# CCM_0001.net
KiCad netlist of a schematic drawn in EAGLE
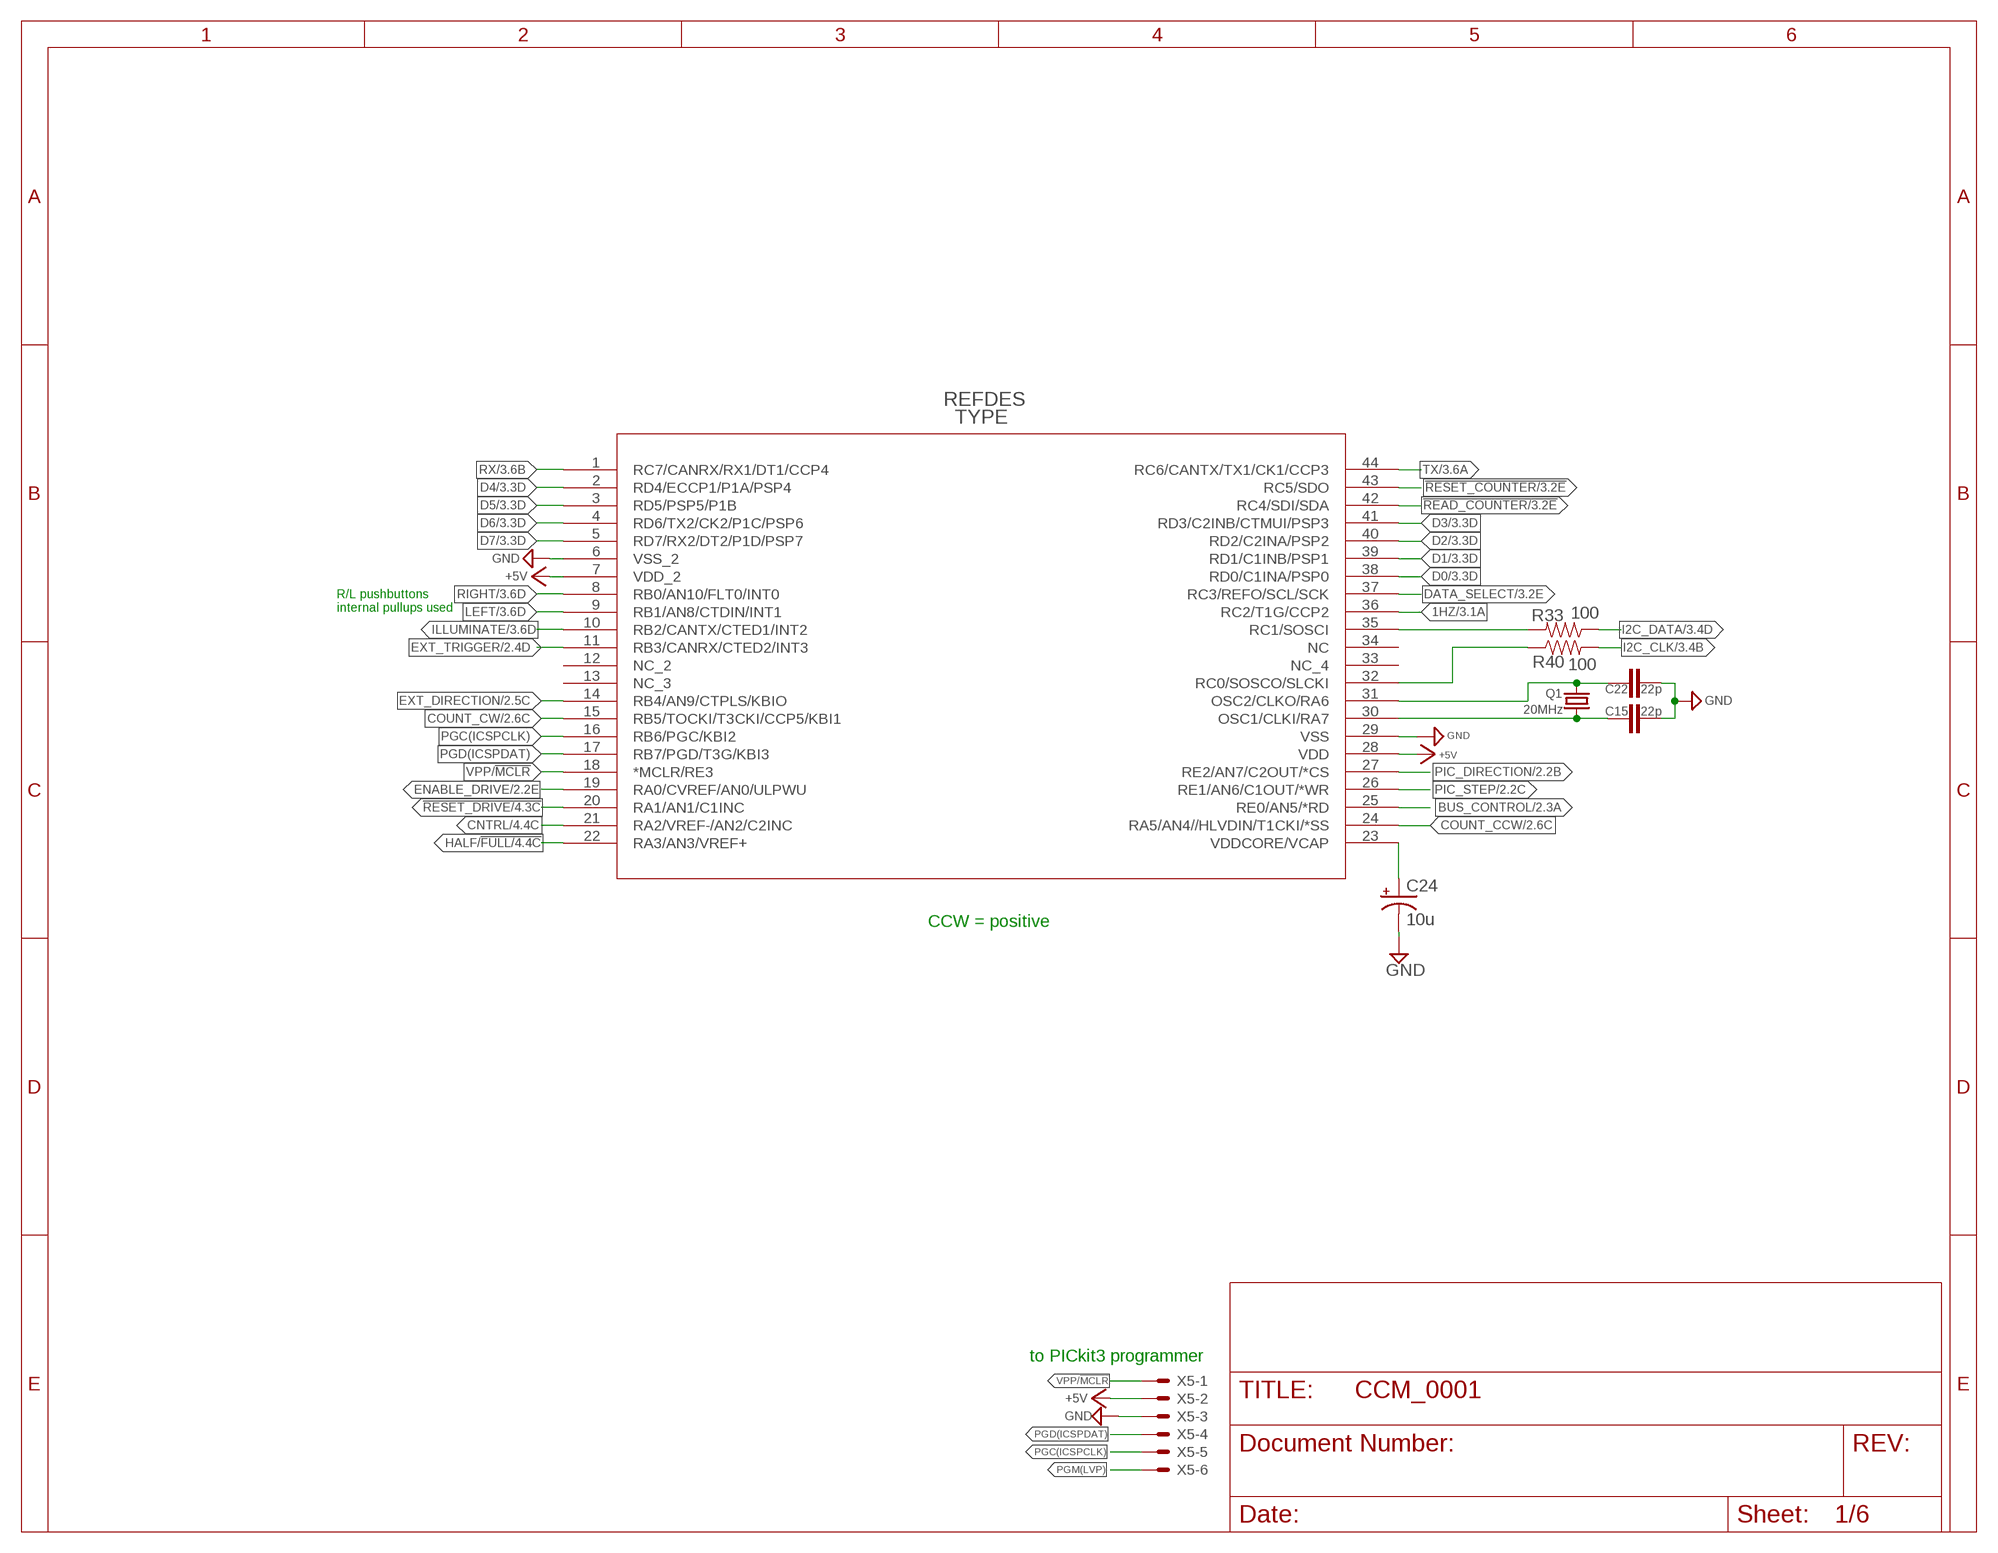
[diagram p0: schematic, sheet 1]
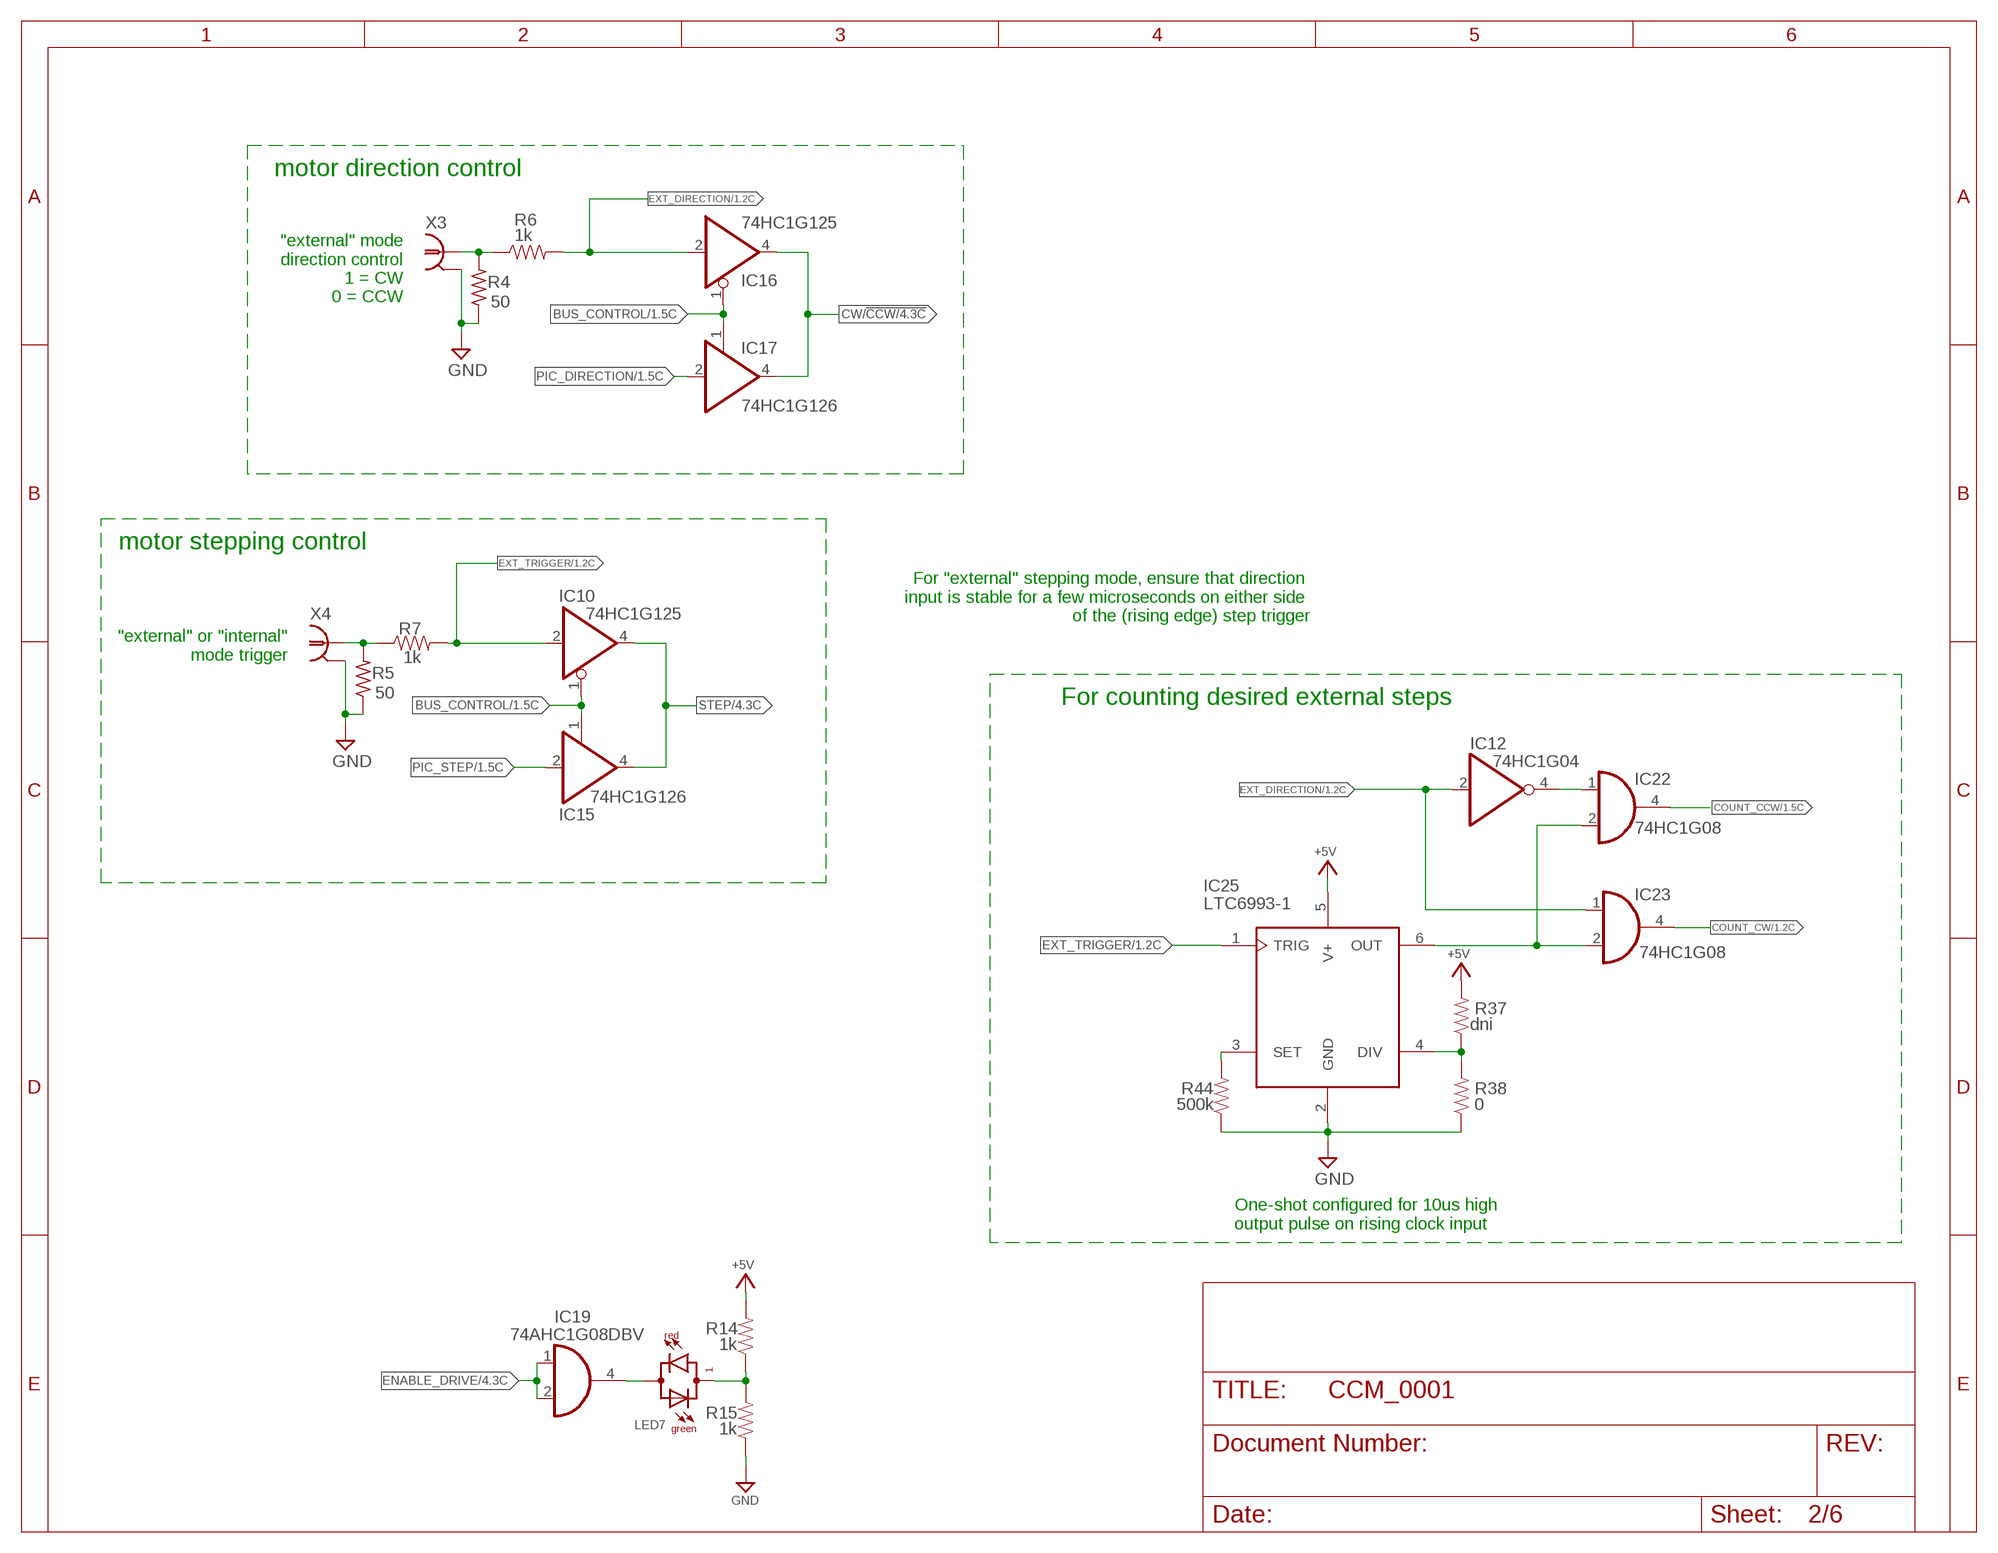
[diagram p1: schematic, sheet 2]
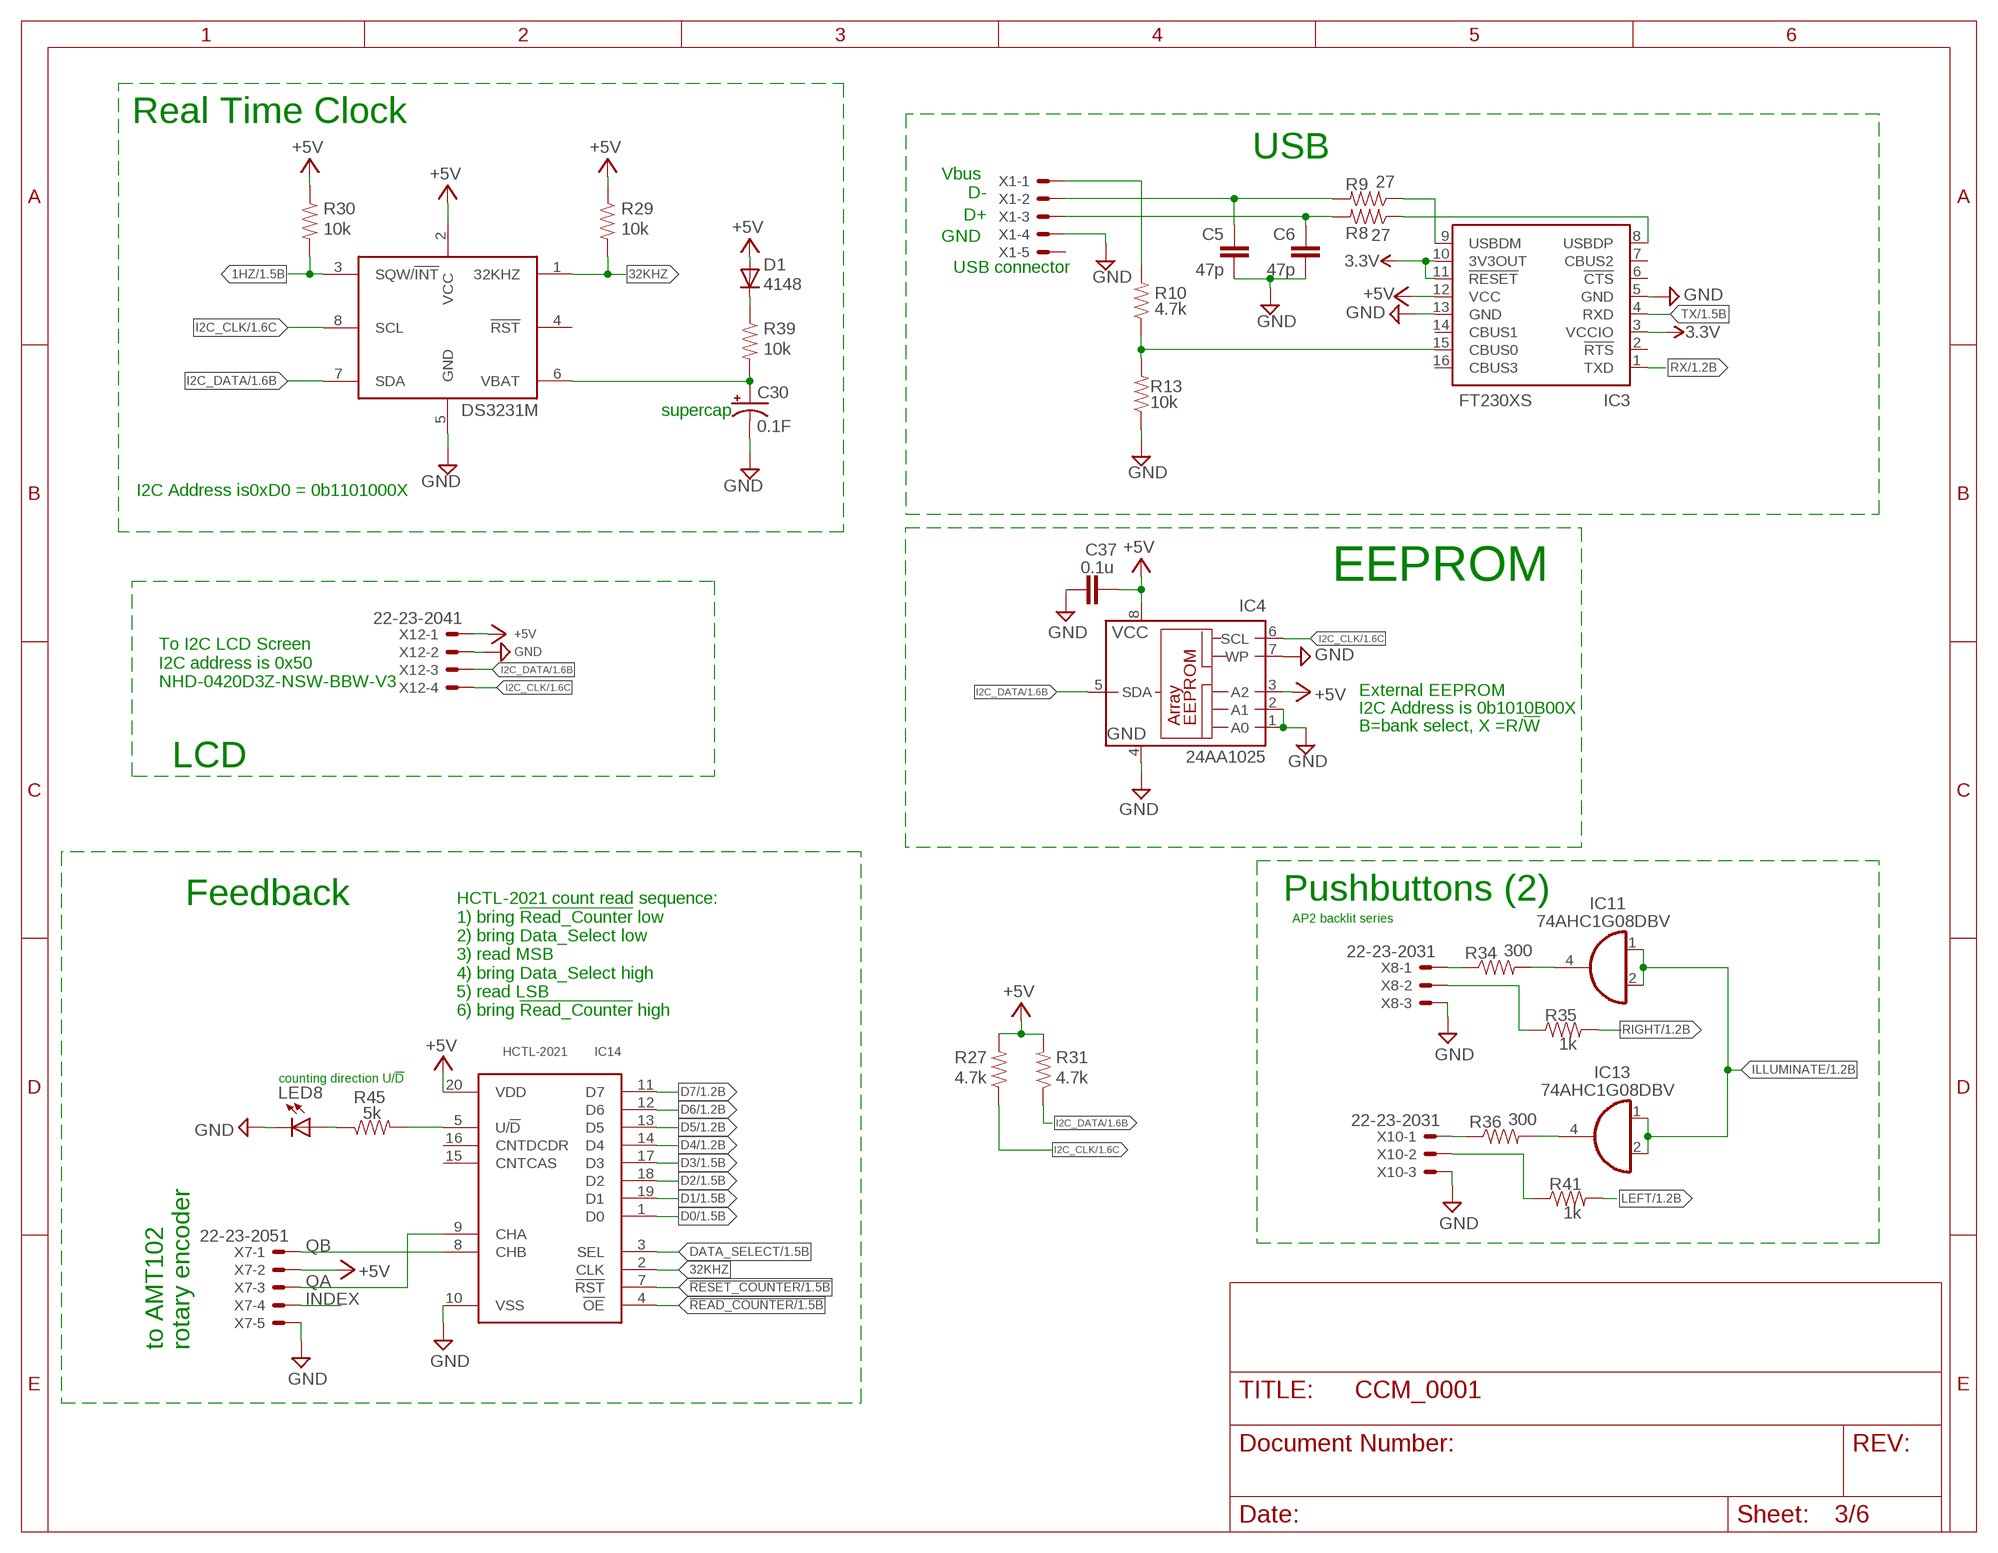
[diagram p2: schematic, sheet 3]
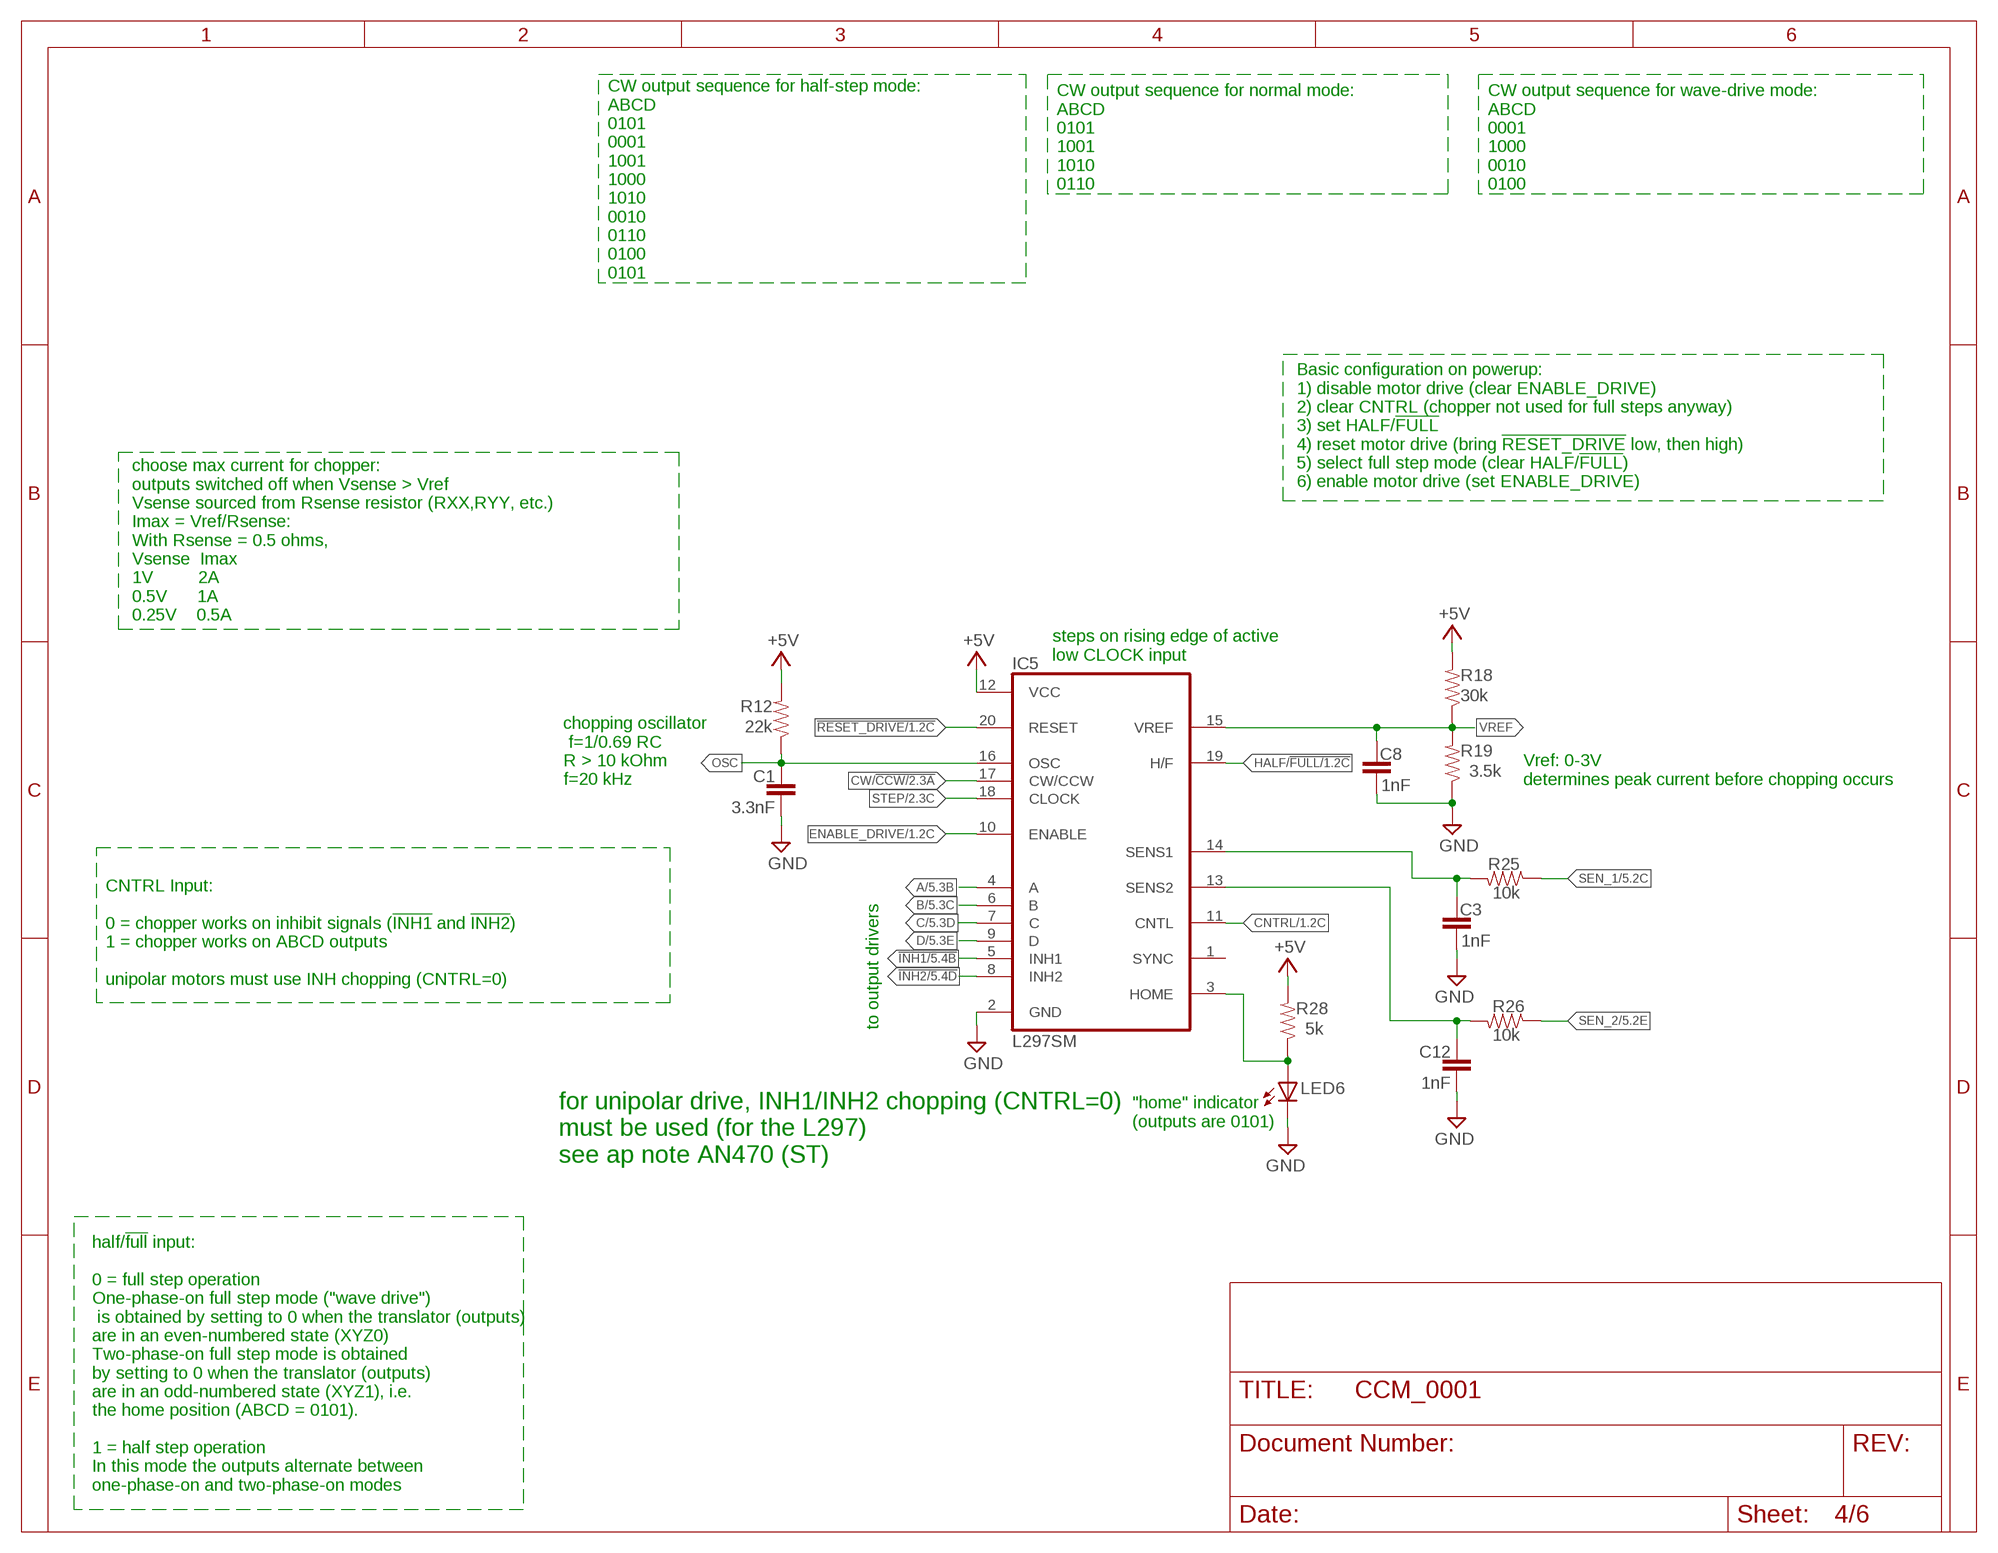
[diagram p3: schematic, sheet 4]
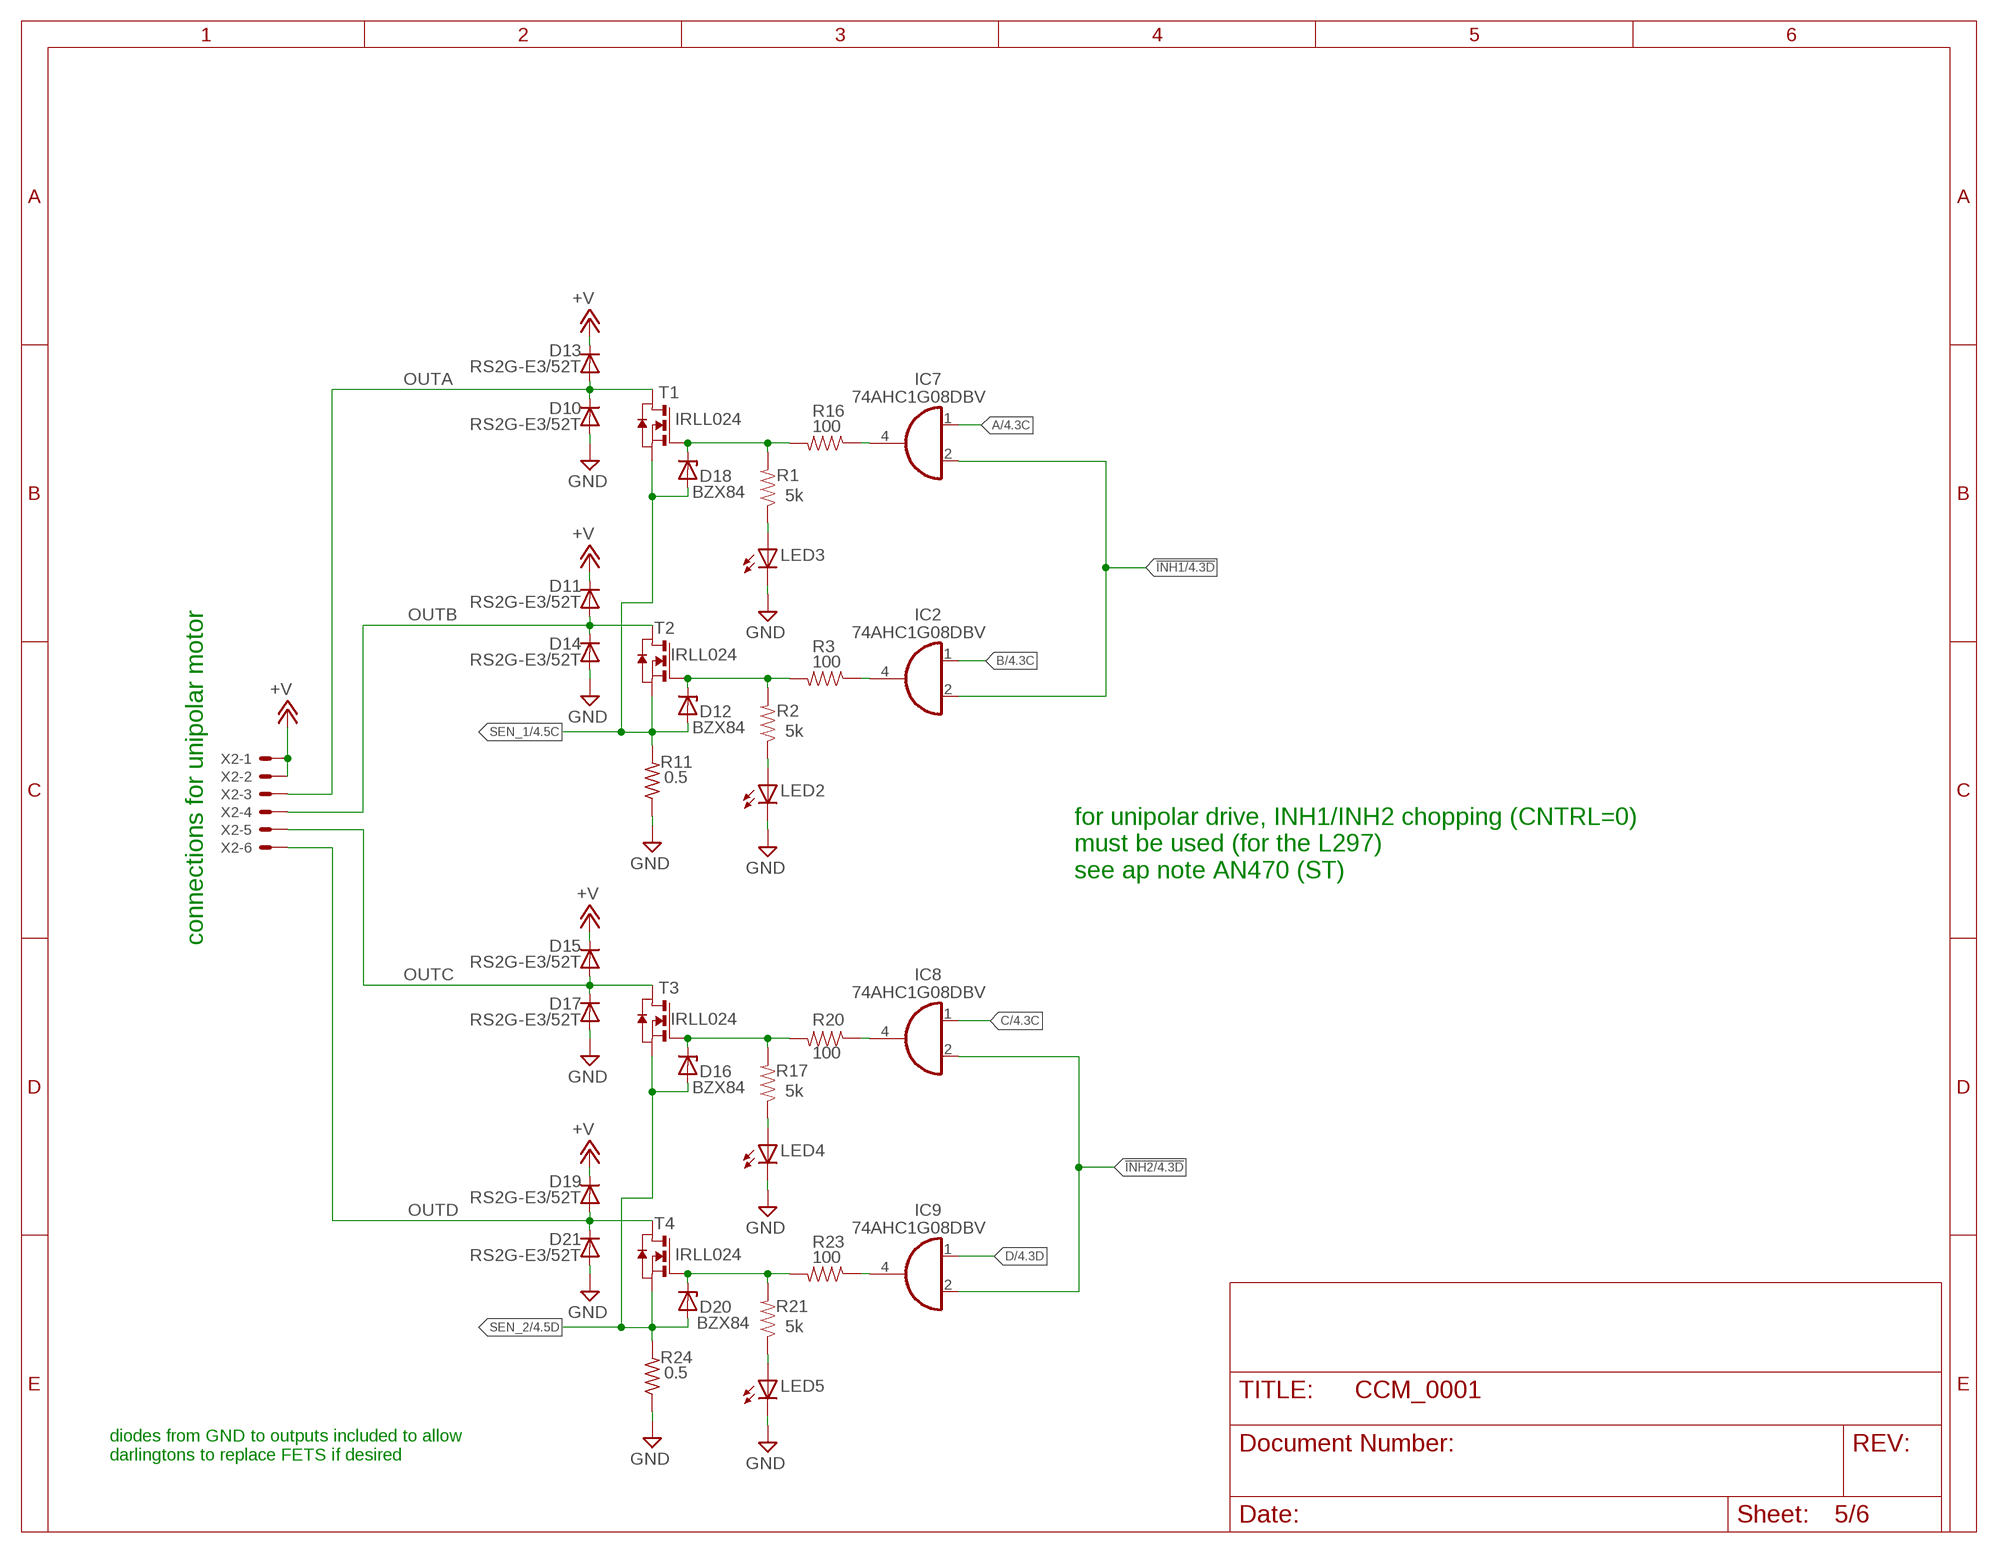
[diagram p4: schematic, sheet 5]
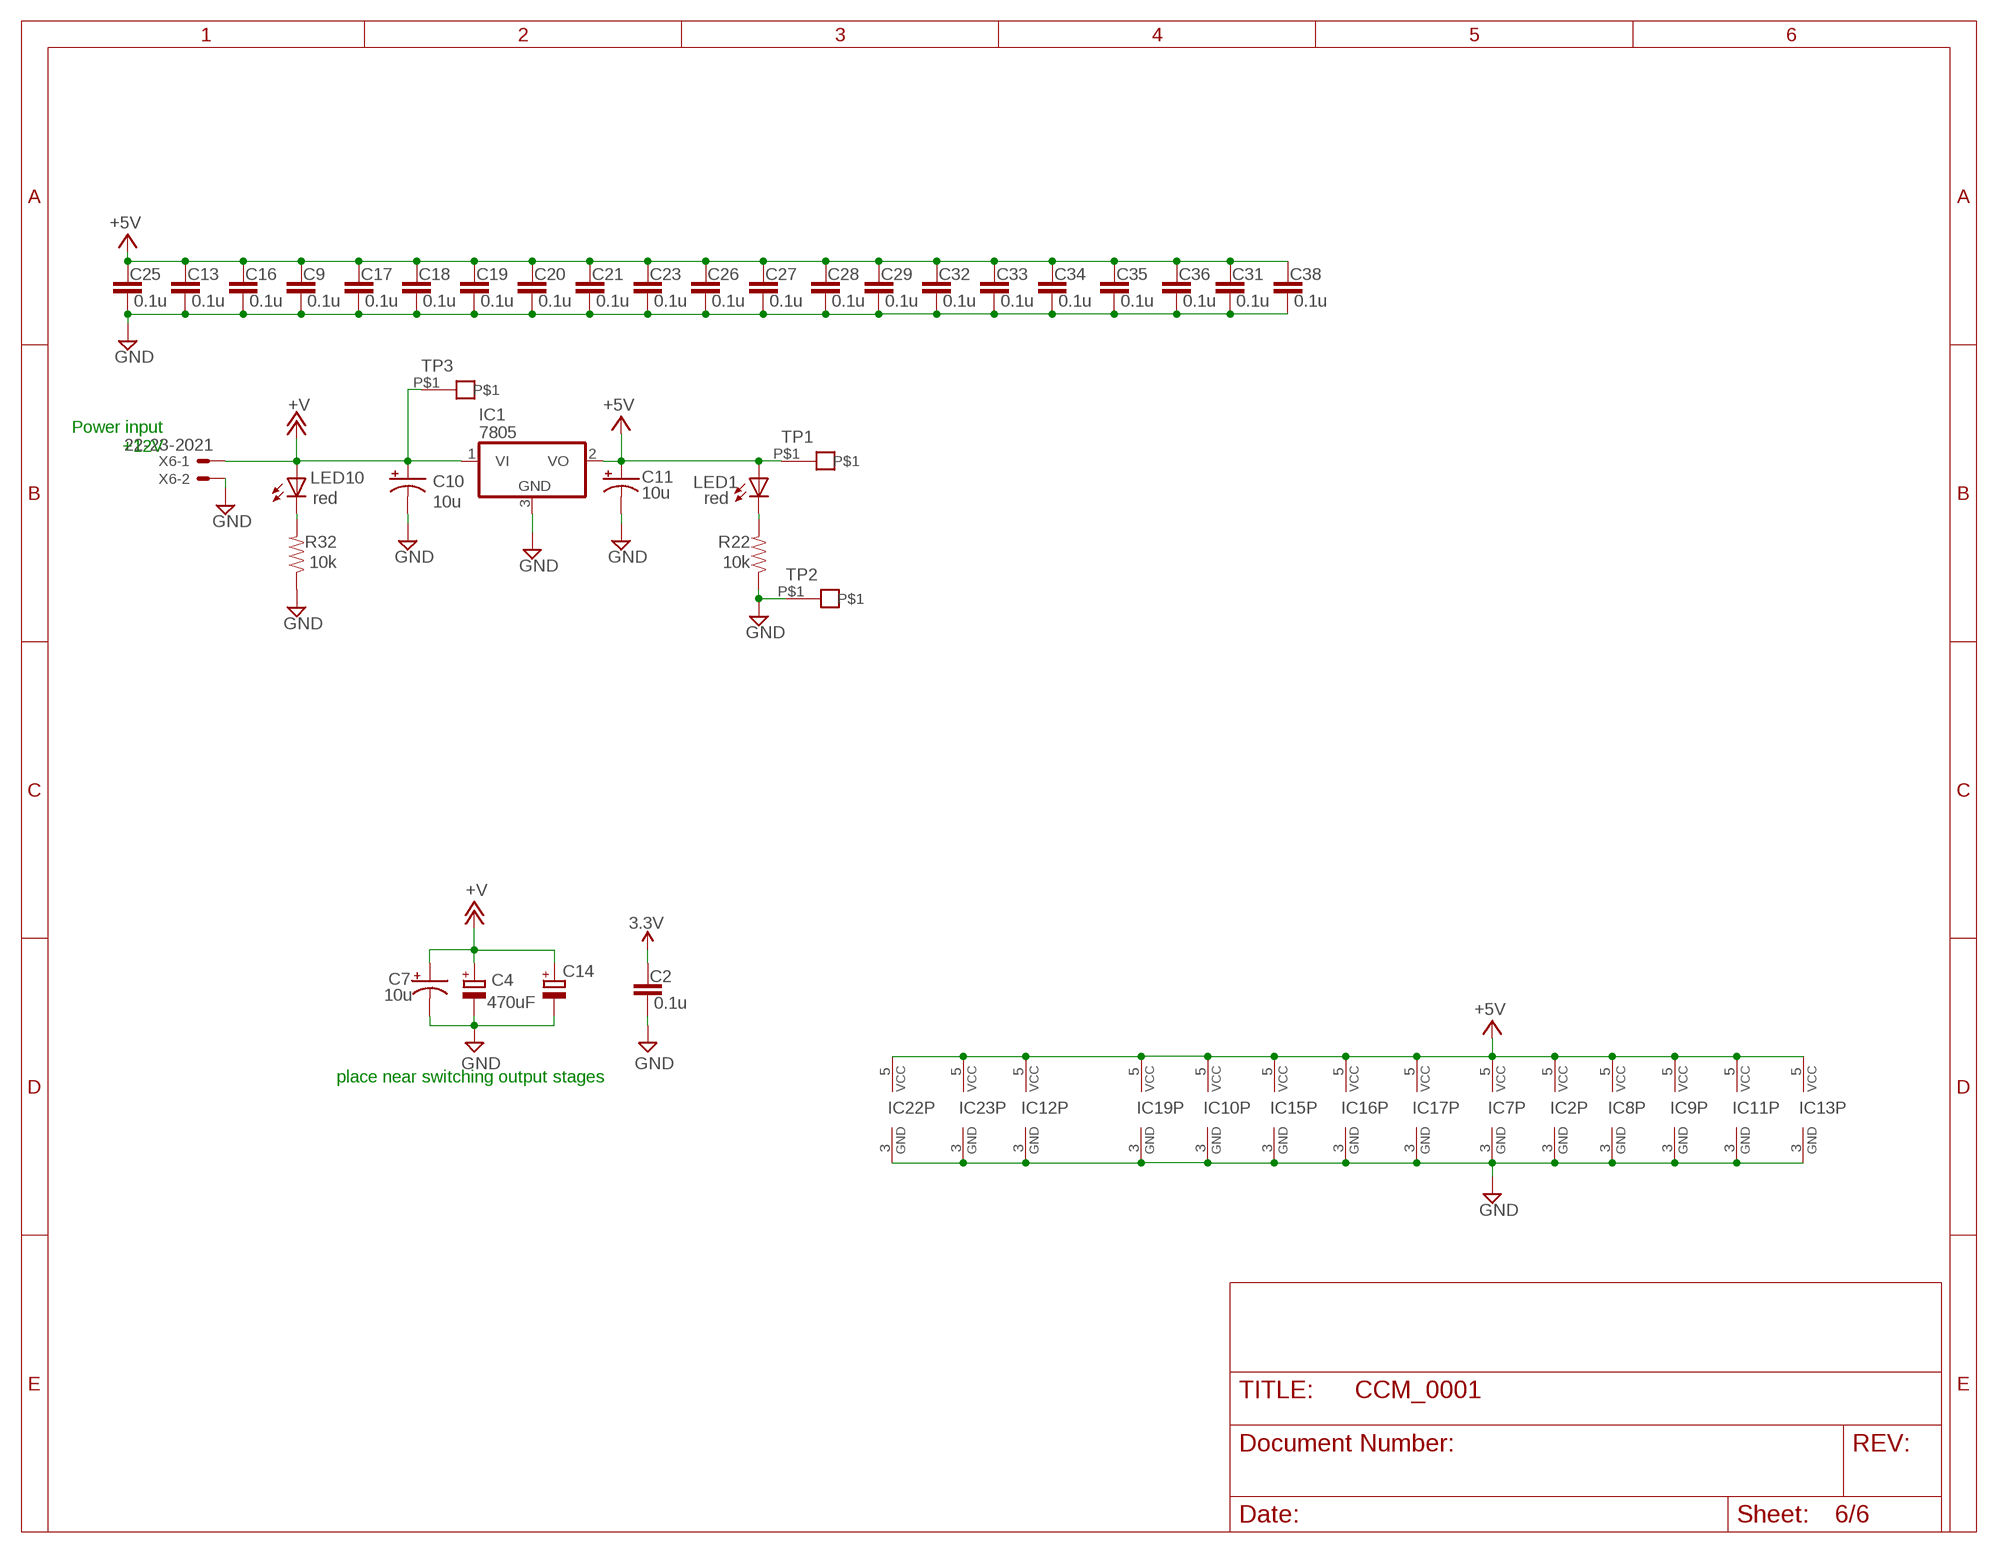
[diagram p5: schematic, sheet 6]

(export (version "E")
  (design (tool "Eeschema 10.0.6"))
  (components
    (comp (ref "C1")
      (value "3.3nF")
      (footprint "eagle-import:0603-CAP")
      (libsource (lib "eagle-import") (part "CAP0603-CAP"))
    )
    (comp (ref "C3")
      (value "1nF")
      (footprint "eagle-import:0603-CAP")
      (libsource (lib "eagle-import") (part "CAP0603-CAP"))
    )
    (comp (ref "C8")
      (value "1nF")
      (footprint "eagle-import:0603-CAP")
      (libsource (lib "eagle-import") (part "CAP0603-CAP"))
    )
    (comp (ref "C12")
      (value "1nF")
      (footprint "eagle-import:0603-CAP")
      (libsource (lib "eagle-import") (part "CAP0603-CAP"))
    )
    (comp (ref "IC5")
      (value "L297SM")
      (footprint "eagle-import:SO20")
      (libsource (lib "eagle-import") (part "L297SM"))
    )
    (comp (ref "LED6")
      (value "red")
      (footprint "eagle-import:CHIPLED_0603")
      (libsource (lib "eagle-import") (part "LEDCHIPLED_0603"))
    )
    (comp (ref "R12")
      (value "22k")
      (footprint "eagle-import:0603-RES")
      (libsource (lib "eagle-import") (part "RESISTOR0603-RES"))
    )
    (comp (ref "R18")
      (value "30k")
      (footprint "eagle-import:0603-RES")
      (libsource (lib "eagle-import") (part "RESISTOR0603-RES"))
    )
    (comp (ref "R19")
      (value "3.5k")
      (footprint "eagle-import:0603-RES")
      (libsource (lib "eagle-import") (part "RESISTOR0603-RES"))
    )
    (comp (ref "R25")
      (value "10k")
      (footprint "eagle-import:0603-RES")
      (libsource (lib "eagle-import") (part "RESISTOR0603-RES"))
    )
    (comp (ref "R26")
      (value "10k")
      (footprint "eagle-import:0603-RES")
      (libsource (lib "eagle-import") (part "RESISTOR0603-RES"))
    )
    (comp (ref "R28")
      (value "5k")
      (footprint "eagle-import:0603-RES")
      (libsource (lib "eagle-import") (part "RESISTOR0603-RES"))
    )
    (comp (ref "C15")
      (value "22p")
      (footprint "eagle-import:0603-CAP")
      (libsource (lib "eagle-import") (part "CAP0603-CAP"))
    )
    (comp (ref "C22")
      (value "22p")
      (footprint "eagle-import:0603-CAP")
      (libsource (lib "eagle-import") (part "CAP0603-CAP"))
    )
    (comp (ref "C24")
      (value "10u")
      (footprint "eagle-import:EIA3216")
      (libsource (lib "eagle-import") (part "CAP_POL1206"))
    )
    (comp (ref "IC18")
      (value "PIC18F46K80")
      (footprint "eagle-import:TQFP44_MC")
      (libsource (lib "eagle-import") (part "PIC18F46K80"))
    )
    (comp (ref "Q1")
      (value "20MHz")
      (footprint "eagle-import:TC26V")
      (libsource (lib "eagle-import") (part "CRYSTALTC26V"))
    )
    (comp (ref "R33")
      (value "100")
      (footprint "eagle-import:0603-RES")
      (libsource (lib "eagle-import") (part "RESISTOR0603-RES"))
    )
    (comp (ref "R40")
      (value "100")
      (footprint "eagle-import:0603-RES")
      (libsource (lib "eagle-import") (part "RESISTOR0603-RES"))
    )
    (comp (ref "X5")
      (value "22-23-2061")
      (footprint "eagle-import:22-23-2061")
      (fields (field (name "MF") "MOLEX"))
      (libsource (lib "eagle-import") (part "22-23-2061"))
    )
    (comp (ref "C5")
      (value "47p")
      (footprint "eagle-import:0603-CAP")
      (libsource (lib "eagle-import") (part "CAP0603-CAP"))
    )
    (comp (ref "C6")
      (value "47p")
      (footprint "eagle-import:0603-CAP")
      (libsource (lib "eagle-import") (part "CAP0603-CAP"))
    )
    (comp (ref "C30")
      (value "0.1F")
      (footprint "eagle-import:P128-60")
      (libsource (lib "eagle-import") (part "CPOL-USP128-60"))
    )
    (comp (ref "C37")
      (value "0.1u")
      (footprint "eagle-import:0603-CAP")
      (libsource (lib "eagle-import") (part "CAP0603-CAP"))
    )
    (comp (ref "D1")
      (value "4148")
      (footprint "eagle-import:SOT23-3")
      (libsource (lib "eagle-import") (part "DIODESOT23"))
    )
    (comp (ref "IC3")
      (value "FT230XS")
      (footprint "eagle-import:SSOP16")
      (libsource (lib "eagle-import") (part "FT230XS"))
    )
    (comp (ref "IC4")
      (value "24AA1025")
      (footprint "eagle-import:SO-08")
      (fields (field (name "MF") "MICROCHIP") (field (name "MPN") "24AA16-I/SN"))
      (libsource (lib "eagle-import") (part "24SNAA16"))
    )
    (comp (ref "IC6")
      (value "DS3231M")
      (footprint "eagle-import:8-SOIC")
      (libsource (lib "eagle-import") (part "DS3231M"))
    )
    (comp (ref "IC11")
      (value "74AHC1G08DBV")
      (footprint "eagle-import:SOT23-5")
      (libsource (lib "eagle-import") (part "741G08DBVAHC"))
    )
    (comp (ref "IC13")
      (value "74AHC1G08DBV")
      (footprint "eagle-import:SOT23-5")
      (libsource (lib "eagle-import") (part "741G08DBVAHC"))
    )
    (comp (ref "IC14")
      (value "HCTL-2021")
      (footprint "eagle-import:PLCC20")
      (libsource (lib "eagle-import") (part "HCTL-2021"))
    )
    (comp (ref "LED8")
      (value "red")
      (footprint "eagle-import:CHIPLED_0603")
      (libsource (lib "eagle-import") (part "LEDCHIPLED_0603"))
    )
    (comp (ref "R8")
      (value "27")
      (footprint "eagle-import:0603-RES")
      (libsource (lib "eagle-import") (part "RESISTOR0603-RES"))
    )
    (comp (ref "R9")
      (value "27")
      (footprint "eagle-import:0603-RES")
      (libsource (lib "eagle-import") (part "RESISTOR0603-RES"))
    )
    (comp (ref "R10")
      (value "4.7k")
      (footprint "eagle-import:0603-RES")
      (libsource (lib "eagle-import") (part "RESISTOR0603-RES"))
    )
    (comp (ref "R13")
      (value "10k")
      (footprint "eagle-import:0603-RES")
      (libsource (lib "eagle-import") (part "RESISTOR0603-RES"))
    )
    (comp (ref "R27")
      (value "4.7k")
      (footprint "eagle-import:0603-RES")
      (libsource (lib "eagle-import") (part "RESISTOR0603-RES"))
    )
    (comp (ref "R29")
      (value "10k")
      (footprint "eagle-import:0603-RES")
      (libsource (lib "eagle-import") (part "RESISTOR0603-RES"))
    )
    (comp (ref "R30")
      (value "10k")
      (footprint "eagle-import:0603-RES")
      (libsource (lib "eagle-import") (part "RESISTOR0603-RES"))
    )
    (comp (ref "R31")
      (value "4.7k")
      (footprint "eagle-import:0603-RES")
      (libsource (lib "eagle-import") (part "RESISTOR0603-RES"))
    )
    (comp (ref "R34")
      (value "300")
      (footprint "eagle-import:0603-RES")
      (libsource (lib "eagle-import") (part "RESISTOR0603-RES"))
    )
    (comp (ref "R35")
      (value "1k")
      (footprint "eagle-import:0603-RES")
      (libsource (lib "eagle-import") (part "RESISTOR0603-RES"))
    )
    (comp (ref "R36")
      (value "300")
      (footprint "eagle-import:0603-RES")
      (libsource (lib "eagle-import") (part "RESISTOR0603-RES"))
    )
    (comp (ref "R39")
      (value "10k")
      (footprint "eagle-import:0603-RES")
      (libsource (lib "eagle-import") (part "RESISTOR0603-RES"))
    )
    (comp (ref "R41")
      (value "1k")
      (footprint "eagle-import:0603-RES")
      (libsource (lib "eagle-import") (part "RESISTOR0603-RES"))
    )
    (comp (ref "R45")
      (value "5k")
      (footprint "eagle-import:0603-RES")
      (libsource (lib "eagle-import") (part "RESISTOR0603-RES"))
    )
    (comp (ref "X1")
      (value "22-23-2051")
      (footprint "eagle-import:22-23-2051")
      (fields (field (name "MF") "MOLEX"))
      (libsource (lib "eagle-import") (part "22-23-2051"))
    )
    (comp (ref "X7")
      (value "22-23-2051")
      (footprint "eagle-import:22-23-2051")
      (fields (field (name "MF") "MOLEX"))
      (libsource (lib "eagle-import") (part "22-23-2051"))
    )
    (comp (ref "X8")
      (value "22-23-2031")
      (footprint "eagle-import:22-23-2031")
      (fields (field (name "MF") "MOLEX"))
      (libsource (lib "eagle-import") (part "22-23-2031"))
    )
    (comp (ref "X10")
      (value "22-23-2031")
      (footprint "eagle-import:22-23-2031")
      (fields (field (name "MF") "MOLEX"))
      (libsource (lib "eagle-import") (part "22-23-2031"))
    )
    (comp (ref "X12")
      (value "22-23-2041")
      (footprint "eagle-import:22-23-2041")
      (fields (field (name "MF") "MOLEX"))
      (libsource (lib "eagle-import") (part "22-23-2041"))
    )
    (comp (ref "C2")
      (value "0.1u")
      (footprint "eagle-import:0603-CAP")
      (libsource (lib "eagle-import") (part "CAP0603-CAP"))
    )
    (comp (ref "C4")
      (value "470uF")
      (footprint "eagle-import:SANYO-OSCON_SMD_F8")
      (libsource (lib "eagle-import") (part "CPOL-EUSANYO_SMD_F8"))
    )
    (comp (ref "C7")
      (value "10u")
      (footprint "eagle-import:EIA3216")
      (libsource (lib "eagle-import") (part "CAP_POL1206"))
    )
    (comp (ref "C9")
      (value "0.1u")
      (footprint "eagle-import:0603-CAP")
      (libsource (lib "eagle-import") (part "CAP0603-CAP"))
    )
    (comp (ref "C10")
      (value "10u")
      (footprint "eagle-import:EIA3216")
      (libsource (lib "eagle-import") (part "CAP_POL1206"))
    )
    (comp (ref "C11")
      (value "10u")
      (footprint "eagle-import:EIA3216")
      (libsource (lib "eagle-import") (part "CAP_POL1206"))
    )
    (comp (ref "C13")
      (value "0.1u")
      (footprint "eagle-import:0603-CAP")
      (libsource (lib "eagle-import") (part "CAP0603-CAP"))
    )
    (comp (ref "C14")
      (value "CPOL-EUE5-13")
      (footprint "eagle-import:E5-13")
      (libsource (lib "eagle-import") (part "resistor_CPOL-EUE5-13"))
    )
    (comp (ref "C16")
      (value "0.1u")
      (footprint "eagle-import:0603-CAP")
      (libsource (lib "eagle-import") (part "CAP0603-CAP"))
    )
    (comp (ref "C17")
      (value "0.1u")
      (footprint "eagle-import:0603-CAP")
      (libsource (lib "eagle-import") (part "CAP0603-CAP"))
    )
    (comp (ref "C18")
      (value "0.1u")
      (footprint "eagle-import:0603-CAP")
      (libsource (lib "eagle-import") (part "CAP0603-CAP"))
    )
    (comp (ref "C19")
      (value "0.1u")
      (footprint "eagle-import:0603-CAP")
      (libsource (lib "eagle-import") (part "CAP0603-CAP"))
    )
    (comp (ref "C20")
      (value "0.1u")
      (footprint "eagle-import:0603-CAP")
      (libsource (lib "eagle-import") (part "CAP0603-CAP"))
    )
    (comp (ref "C21")
      (value "0.1u")
      (footprint "eagle-import:0603-CAP")
      (libsource (lib "eagle-import") (part "CAP0603-CAP"))
    )
    (comp (ref "C23")
      (value "0.1u")
      (footprint "eagle-import:0603-CAP")
      (libsource (lib "eagle-import") (part "CAP0603-CAP"))
    )
    (comp (ref "C25")
      (value "0.1u")
      (footprint "eagle-import:0603-CAP")
      (libsource (lib "eagle-import") (part "CAP0603-CAP"))
    )
    (comp (ref "C26")
      (value "0.1u")
      (footprint "eagle-import:0603-CAP")
      (libsource (lib "eagle-import") (part "CAP0603-CAP"))
    )
    (comp (ref "C27")
      (value "0.1u")
      (footprint "eagle-import:0603-CAP")
      (libsource (lib "eagle-import") (part "CAP0603-CAP"))
    )
    (comp (ref "C28")
      (value "0.1u")
      (footprint "eagle-import:0603-CAP")
      (libsource (lib "eagle-import") (part "CAP0603-CAP"))
    )
    (comp (ref "C29")
      (value "0.1u")
      (footprint "eagle-import:0603-CAP")
      (libsource (lib "eagle-import") (part "CAP0603-CAP"))
    )
    (comp (ref "C31")
      (value "0.1u")
      (footprint "eagle-import:0603-CAP")
      (libsource (lib "eagle-import") (part "CAP0603-CAP"))
    )
    (comp (ref "C32")
      (value "0.1u")
      (footprint "eagle-import:0603-CAP")
      (libsource (lib "eagle-import") (part "CAP0603-CAP"))
    )
    (comp (ref "C33")
      (value "0.1u")
      (footprint "eagle-import:0603-CAP")
      (libsource (lib "eagle-import") (part "CAP0603-CAP"))
    )
    (comp (ref "C34")
      (value "0.1u")
      (footprint "eagle-import:0603-CAP")
      (libsource (lib "eagle-import") (part "CAP0603-CAP"))
    )
    (comp (ref "C35")
      (value "0.1u")
      (footprint "eagle-import:0603-CAP")
      (libsource (lib "eagle-import") (part "CAP0603-CAP"))
    )
    (comp (ref "C36")
      (value "0.1u")
      (footprint "eagle-import:0603-CAP")
      (libsource (lib "eagle-import") (part "CAP0603-CAP"))
    )
    (comp (ref "C38")
      (value "0.1u")
      (footprint "eagle-import:0603-CAP")
      (libsource (lib "eagle-import") (part "CAP0603-CAP"))
    )
    (comp (ref "IC1")
      (value "7805")
      (footprint "eagle-import:TO252")
      (libsource (lib "eagle-import") (part "78DT24"))
    )
    (comp (ref "IC2")
      (value "74AHC1G08DBV")
      (footprint "eagle-import:SOT23-5")
      (libsource (lib "eagle-import") (part "741G08DBVAHC"))
    )
    (comp (ref "IC7")
      (value "74AHC1G08DBV")
      (footprint "eagle-import:SOT23-5")
      (libsource (lib "eagle-import") (part "741G08DBVAHC"))
    )
    (comp (ref "IC8")
      (value "74AHC1G08DBV")
      (footprint "eagle-import:SOT23-5")
      (libsource (lib "eagle-import") (part "741G08DBVAHC"))
    )
    (comp (ref "IC9")
      (value "74AHC1G08DBV")
      (footprint "eagle-import:SOT23-5")
      (libsource (lib "eagle-import") (part "741G08DBVAHC"))
    )
    (comp (ref "IC10")
      (value "74HC1G125")
      (footprint "eagle-import:SOT23-5")
      (libsource (lib "eagle-import") (part "741G125DBVAHC"))
    )
    (comp (ref "IC12")
      (value "74HC1G04")
      (footprint "eagle-import:SOT23-5")
      (libsource (lib "eagle-import") (part "741G04DBVAHC"))
    )
    (comp (ref "IC15")
      (value "74HC1G126")
      (footprint "eagle-import:SOT23-5")
      (libsource (lib "eagle-import") (part "741G126DBVAHC"))
    )
    (comp (ref "IC16")
      (value "74HC1G125")
      (footprint "eagle-import:SOT23-5")
      (libsource (lib "eagle-import") (part "741G125DBVAHC"))
    )
    (comp (ref "IC17")
      (value "74HC1G126")
      (footprint "eagle-import:SOT23-5")
      (libsource (lib "eagle-import") (part "741G126DBVAHC"))
    )
    (comp (ref "IC19")
      (value "74AHC1G08DBV")
      (footprint "eagle-import:SOT23-5")
      (libsource (lib "eagle-import") (part "741G08DBVAHC"))
    )
    (comp (ref "IC22")
      (value "74HC1G08")
      (footprint "eagle-import:SOT23-5")
      (libsource (lib "eagle-import") (part "741G08DBVAHC"))
    )
    (comp (ref "IC23")
      (value "74HC1G08")
      (footprint "eagle-import:SOT23-5")
      (libsource (lib "eagle-import") (part "741G08DBVAHC"))
    )
    (comp (ref "LED1")
      (value "red")
      (footprint "eagle-import:CHIPLED_0603")
      (libsource (lib "eagle-import") (part "LEDCHIPLED_0603"))
    )
    (comp (ref "LED10")
      (value "red")
      (footprint "eagle-import:CHIPLED_0603")
      (libsource (lib "eagle-import") (part "LEDCHIPLED_0603"))
    )
    (comp (ref "R22")
      (value "10k")
      (footprint "eagle-import:0603-RES")
      (libsource (lib "eagle-import") (part "RESISTOR0603-RES"))
    )
    (comp (ref "R32")
      (value "10k")
      (footprint "eagle-import:0603-RES")
      (libsource (lib "eagle-import") (part "RESISTOR0603-RES"))
    )
    (comp (ref "TP1")
      (value "TESTPOINT")
      (footprint "eagle-import:TESTPOINT")
      (libsource (lib "eagle-import") (part "TESTPOINT"))
    )
    (comp (ref "TP2")
      (value "TESTPOINT")
      (footprint "eagle-import:TESTPOINT")
      (libsource (lib "eagle-import") (part "TESTPOINT"))
    )
    (comp (ref "TP3")
      (value "TESTPOINT")
      (footprint "eagle-import:TESTPOINT")
      (libsource (lib "eagle-import") (part "TESTPOINT"))
    )
    (comp (ref "X6")
      (value "22-23-2021")
      (footprint "eagle-import:22-23-2021")
      (fields (field (name "MF") "MOLEX"))
      (libsource (lib "eagle-import") (part "22-23-2021"))
    )
    (comp (ref "D10")
      (value "RS2G-E3/52T")
      (footprint "eagle-import:DO214AA")
      (libsource (lib "eagle-import") (part "DIODE-DO214AA"))
    )
    (comp (ref "D11")
      (value "RS2G-E3/52T")
      (footprint "eagle-import:DO214AA")
      (libsource (lib "eagle-import") (part "DIODE-DO214AA"))
    )
    (comp (ref "D12")
      (value "BZX84")
      (footprint "eagle-import:SOT23")
      (libsource (lib "eagle-import") (part "ZENER-DIODESOT23"))
    )
    (comp (ref "D13")
      (value "RS2G-E3/52T")
      (footprint "eagle-import:DO214AA")
      (libsource (lib "eagle-import") (part "DIODE-DO214AA"))
    )
    (comp (ref "D14")
      (value "RS2G-E3/52T")
      (footprint "eagle-import:DO214AA")
      (libsource (lib "eagle-import") (part "DIODE-DO214AA"))
    )
    (comp (ref "D15")
      (value "RS2G-E3/52T")
      (footprint "eagle-import:DO214AA")
      (libsource (lib "eagle-import") (part "DIODE-DO214AA"))
    )
    (comp (ref "D16")
      (value "BZX84")
      (footprint "eagle-import:SOT23")
      (libsource (lib "eagle-import") (part "ZENER-DIODESOT23"))
    )
    (comp (ref "D17")
      (value "RS2G-E3/52T")
      (footprint "eagle-import:DO214AA")
      (libsource (lib "eagle-import") (part "DIODE-DO214AA"))
    )
    (comp (ref "D18")
      (value "BZX84")
      (footprint "eagle-import:SOT23")
      (libsource (lib "eagle-import") (part "ZENER-DIODESOT23"))
    )
    (comp (ref "D19")
      (value "RS2G-E3/52T")
      (footprint "eagle-import:DO214AA")
      (libsource (lib "eagle-import") (part "DIODE-DO214AA"))
    )
    (comp (ref "D20")
      (value "BZX84")
      (footprint "eagle-import:SOT23")
      (libsource (lib "eagle-import") (part "ZENER-DIODESOT23"))
    )
    (comp (ref "D21")
      (value "RS2G-E3/52T")
      (footprint "eagle-import:DO214AA")
      (libsource (lib "eagle-import") (part "DIODE-DO214AA"))
    )
    (comp (ref "LED2")
      (value "red")
      (footprint "eagle-import:CHIPLED_0603")
      (libsource (lib "eagle-import") (part "LEDCHIPLED_0603"))
    )
    (comp (ref "LED3")
      (value "red")
      (footprint "eagle-import:CHIPLED_0603")
      (libsource (lib "eagle-import") (part "LEDCHIPLED_0603"))
    )
    (comp (ref "LED4")
      (value "red")
      (footprint "eagle-import:CHIPLED_0603")
      (libsource (lib "eagle-import") (part "LEDCHIPLED_0603"))
    )
    (comp (ref "LED5")
      (value "red")
      (footprint "eagle-import:CHIPLED_0603")
      (libsource (lib "eagle-import") (part "LEDCHIPLED_0603"))
    )
    (comp (ref "R1")
      (value "5k")
      (footprint "eagle-import:0603-RES")
      (libsource (lib "eagle-import") (part "RESISTOR0603-RES"))
    )
    (comp (ref "R2")
      (value "5k")
      (footprint "eagle-import:0603-RES")
      (libsource (lib "eagle-import") (part "RESISTOR0603-RES"))
    )
    (comp (ref "R3")
      (value "100")
      (footprint "eagle-import:0603-RES")
      (libsource (lib "eagle-import") (part "RESISTOR0603-RES"))
    )
    (comp (ref "R11")
      (value "0.5")
      (footprint "eagle-import:R2512")
      (libsource (lib "eagle-import") (part "resistor_R-US_R2512"))
    )
    (comp (ref "R16")
      (value "100")
      (footprint "eagle-import:0603-RES")
      (libsource (lib "eagle-import") (part "RESISTOR0603-RES"))
    )
    (comp (ref "R17")
      (value "5k")
      (footprint "eagle-import:0603-RES")
      (libsource (lib "eagle-import") (part "RESISTOR0603-RES"))
    )
    (comp (ref "R20")
      (value "100")
      (footprint "eagle-import:0603-RES")
      (libsource (lib "eagle-import") (part "RESISTOR0603-RES"))
    )
    (comp (ref "R21")
      (value "5k")
      (footprint "eagle-import:0603-RES")
      (libsource (lib "eagle-import") (part "RESISTOR0603-RES"))
    )
    (comp (ref "R23")
      (value "100")
      (footprint "eagle-import:0603-RES")
      (libsource (lib "eagle-import") (part "RESISTOR0603-RES"))
    )
    (comp (ref "R24")
      (value "0.5")
      (footprint "eagle-import:R2512")
      (libsource (lib "eagle-import") (part "resistor_R-US_R2512"))
    )
    (comp (ref "T1")
      (value "IRLL024")
      (footprint "eagle-import:SOT223")
      (libsource (lib "eagle-import") (part "NMOSSOT223"))
    )
    (comp (ref "T2")
      (value "IRLL024")
      (footprint "eagle-import:SOT223")
      (libsource (lib "eagle-import") (part "NMOSSOT223"))
    )
    (comp (ref "T3")
      (value "IRLL024")
      (footprint "eagle-import:SOT223")
      (libsource (lib "eagle-import") (part "NMOSSOT223"))
    )
    (comp (ref "T4")
      (value "IRLL024")
      (footprint "eagle-import:SOT223")
      (libsource (lib "eagle-import") (part "NMOSSOT223"))
    )
    (comp (ref "X2")
      (value "22-23-2061")
      (footprint "eagle-import:22-23-2061")
      (fields (field (name "MF") "MOLEX"))
      (libsource (lib "eagle-import") (part "22-23-2061"))
    )
    (comp (ref "IC25")
      (value "LTC6993-1")
      (footprint "eagle-import:SOT23-6")
      (libsource (lib "eagle-import") (part "LTC6993-1"))
    )
    (comp (ref "LED7")
      (value "BILED")
      (footprint "eagle-import:22-23-2021")
      (libsource (lib "eagle-import") (part "BILED"))
    )
    (comp (ref "R4")
      (value "50")
      (footprint "eagle-import:R2512")
      (libsource (lib "eagle-import") (part "R-US_R2512"))
    )
    (comp (ref "R5")
      (value "50")
      (footprint "eagle-import:R2512")
      (libsource (lib "eagle-import") (part "R-US_R2512"))
    )
    (comp (ref "R6")
      (value "1k")
      (footprint "eagle-import:0603-RES")
      (libsource (lib "eagle-import") (part "RESISTOR0603-RES"))
    )
    (comp (ref "R7")
      (value "1k")
      (footprint "eagle-import:0603-RES")
      (libsource (lib "eagle-import") (part "RESISTOR0603-RES"))
    )
    (comp (ref "R14")
      (value "1k")
      (footprint "eagle-import:0603-RES")
      (libsource (lib "eagle-import") (part "RESISTOR0603-RES"))
    )
    (comp (ref "R15")
      (value "1k")
      (footprint "eagle-import:0603-RES")
      (libsource (lib "eagle-import") (part "RESISTOR0603-RES"))
    )
    (comp (ref "R37")
      (value "dni")
      (footprint "eagle-import:0603-RES")
      (libsource (lib "eagle-import") (part "RESISTOR0603-RES"))
    )
    (comp (ref "R38")
      (value "0")
      (footprint "eagle-import:0603-RES")
      (libsource (lib "eagle-import") (part "RESISTOR0603-RES"))
    )
    (comp (ref "R44")
      (value "500k")
      (footprint "eagle-import:0603-RES")
      (libsource (lib "eagle-import") (part "RESISTOR0603-RES"))
    )
    (comp (ref "X3")
      (value "1-227161-0")
      (footprint "eagle-import:AMP_227161")
      (fields (field (name "MF") "TYCO ELECTRONICS") (field (name "MPN") "1-227161"))
      (libsource (lib "eagle-import") (part "?2271611--0"))
    )
    (comp (ref "X4")
      (value "1-227161-0")
      (footprint "eagle-import:AMP_227161")
      (fields (field (name "MF") "TYCO ELECTRONICS") (field (name "MPN") "1-227161"))
      (libsource (lib "eagle-import") (part "?2271611--0"))
    )
  )
  (nets
    (net (code "1") (name "+5V") (class "Default")
      (node (ref "C11") (pin "A") (pinfunction "+_A") (pintype "passive"))
      (node (ref "C13") (pin "1") (pinfunction "1_1") (pintype "passive"))
      (node (ref "C16") (pin "1") (pinfunction "1_1") (pintype "passive"))
      (node (ref "C17") (pin "1") (pinfunction "1_1") (pintype "passive"))
      (node (ref "C18") (pin "1") (pinfunction "1_1") (pintype "passive"))
      (node (ref "C19") (pin "1") (pinfunction "1_1") (pintype "passive"))
      (node (ref "C20") (pin "1") (pinfunction "1_1") (pintype "passive"))
      (node (ref "C21") (pin "1") (pinfunction "1_1") (pintype "passive"))
      (node (ref "C23") (pin "1") (pinfunction "1_1") (pintype "passive"))
      (node (ref "C25") (pin "1") (pinfunction "1_1") (pintype "passive"))
      (node (ref "C26") (pin "1") (pinfunction "1_1") (pintype "passive"))
      (node (ref "C27") (pin "1") (pinfunction "1_1") (pintype "passive"))
      (node (ref "C28") (pin "1") (pinfunction "1_1") (pintype "passive"))
      (node (ref "C29") (pin "1") (pinfunction "1_1") (pintype "passive"))
      (node (ref "C31") (pin "1") (pinfunction "1_1") (pintype "passive"))
      (node (ref "C32") (pin "1") (pinfunction "1_1") (pintype "passive"))
      (node (ref "C33") (pin "1") (pinfunction "1_1") (pintype "passive"))
      (node (ref "C34") (pin "1") (pinfunction "1_1") (pintype "passive"))
      (node (ref "C35") (pin "1") (pinfunction "1_1") (pintype "passive"))
      (node (ref "C36") (pin "1") (pinfunction "1_1") (pintype "passive"))
      (node (ref "C37") (pin "1") (pinfunction "1_1") (pintype "passive"))
      (node (ref "C38") (pin "1") (pinfunction "1_1") (pintype "passive"))
      (node (ref "C9") (pin "1") (pinfunction "1_1") (pintype "passive"))
      (node (ref "D1") (pin "1") (pinfunction "A_1") (pintype "passive"))
      (node (ref "IC1") (pin "2") (pinfunction "VO_2") (pintype "passive"))
      (node (ref "IC10") (pin "5") (pinfunction "VCC_5") (pintype "power_in"))
      (node (ref "IC11") (pin "5") (pinfunction "VCC_5") (pintype "power_in"))
      (node (ref "IC12") (pin "5") (pinfunction "VCC_5") (pintype "power_in"))
      (node (ref "IC13") (pin "5") (pinfunction "VCC_5") (pintype "power_in"))
      (node (ref "IC14") (pin "20") (pinfunction "VDD_20") (pintype "bidirectional"))
      (node (ref "IC15") (pin "5") (pinfunction "VCC_5") (pintype "power_in"))
      (node (ref "IC16") (pin "5") (pinfunction "VCC_5") (pintype "power_in"))
      (node (ref "IC17") (pin "5") (pinfunction "VCC_5") (pintype "power_in"))
      (node (ref "IC18") (pin "28") (pinfunction "VDD_28") (pintype "passive"))
      (node (ref "IC18") (pin "7") (pinfunction "VDD_2_7") (pintype "passive"))
      (node (ref "IC19") (pin "5") (pinfunction "VCC_5") (pintype "power_in"))
      (node (ref "IC2") (pin "5") (pinfunction "VCC_5") (pintype "power_in"))
      (node (ref "IC22") (pin "5") (pinfunction "VCC_5") (pintype "power_in"))
      (node (ref "IC23") (pin "5") (pinfunction "VCC_5") (pintype "power_in"))
      (node (ref "IC25") (pin "5") (pinfunction "V+_5") (pintype "bidirectional"))
      (node (ref "IC3") (pin "12") (pinfunction "VCC_12") (pintype "power_in"))
      (node (ref "IC4") (pin "3") (pinfunction "A2_3") (pintype "input"))
      (node (ref "IC4") (pin "8") (pinfunction "VCC_8") (pintype "power_in"))
      (node (ref "IC5") (pin "12") (pinfunction "VCC_12") (pintype "power_in"))
      (node (ref "IC6") (pin "2") (pinfunction "VCC_2") (pintype "bidirectional"))
      (node (ref "IC7") (pin "5") (pinfunction "VCC_5") (pintype "power_in"))
      (node (ref "IC8") (pin "5") (pinfunction "VCC_5") (pintype "power_in"))
      (node (ref "IC9") (pin "5") (pinfunction "VCC_5") (pintype "power_in"))
      (node (ref "LED1") (pin "A") (pinfunction "A_A") (pintype "passive"))
      (node (ref "R12") (pin "2") (pinfunction "2_2") (pintype "passive"))
      (node (ref "R14") (pin "2") (pinfunction "2_2") (pintype "passive"))
      (node (ref "R18") (pin "2") (pinfunction "2_2") (pintype "passive"))
      (node (ref "R27") (pin "2") (pinfunction "2_2") (pintype "passive"))
      (node (ref "R28") (pin "2") (pinfunction "2_2") (pintype "passive"))
      (node (ref "R29") (pin "1") (pinfunction "1_1") (pintype "passive"))
      (node (ref "R30") (pin "1") (pinfunction "1_1") (pintype "passive"))
      (node (ref "R31") (pin "2") (pinfunction "2_2") (pintype "passive"))
      (node (ref "R37") (pin "2") (pinfunction "2_2") (pintype "passive"))
      (node (ref "TP1") (pin "P$1") (pinfunction "P$1_P$1") (pintype "bidirectional"))
      (node (ref "X12") (pin "1") (pinfunction "S_1") (pintype "passive"))
      (node (ref "X5") (pin "2") (pinfunction "S_2") (pintype "passive"))
      (node (ref "X7") (pin "2") (pinfunction "S_2") (pintype "passive"))
    )
    (net (code "2") (name "+V") (class "Default")
      (node (ref "C10") (pin "A") (pinfunction "+_A") (pintype "passive"))
      (node (ref "C14") (pin "+") (pinfunction "+_+") (pintype "passive"))
      (node (ref "C4") (pin "+") (pinfunction "+_+") (pintype "passive"))
      (node (ref "C7") (pin "A") (pinfunction "+_A") (pintype "passive"))
      (node (ref "D11") (pin "C") (pinfunction "C_C") (pintype "passive"))
      (node (ref "D13") (pin "C") (pinfunction "C_C") (pintype "passive"))
      (node (ref "D15") (pin "C") (pinfunction "C_C") (pintype "passive"))
      (node (ref "D19") (pin "C") (pinfunction "C_C") (pintype "passive"))
      (node (ref "IC1") (pin "1") (pinfunction "VI_1") (pintype "input"))
      (node (ref "LED10") (pin "A") (pinfunction "A_A") (pintype "passive"))
      (node (ref "TP3") (pin "P$1") (pinfunction "P$1_P$1") (pintype "bidirectional"))
      (node (ref "X2") (pin "1") (pinfunction "S_1") (pintype "passive"))
      (node (ref "X2") (pin "2") (pinfunction "S_2") (pintype "passive"))
      (node (ref "X6") (pin "1") (pinfunction "S_1") (pintype "passive"))
    )
    (net (code "3") (name "1HZ") (class "Default")
      (node (ref "IC18") (pin "36") (pinfunction "RC2/T1G/CCP2_36") (pintype "passive"))
      (node (ref "IC6") (pin "3") (pinfunction "SQW/~{INT}_3") (pintype "bidirectional"))
      (node (ref "R30") (pin "2") (pinfunction "2_2") (pintype "passive"))
    )
    (net (code "4") (name "3.3V") (class "Default")
      (node (ref "C2") (pin "1") (pinfunction "1_1") (pintype "passive"))
      (node (ref "IC3") (pin "10") (pinfunction "3V3OUT_10") (pintype "output"))
      (node (ref "IC3") (pin "11") (pinfunction "~{RESET}_11") (pintype "input"))
      (node (ref "IC3") (pin "3") (pinfunction "VCCIO_3") (pintype "power_in"))
    )
    (net (code "5") (name "32KHZ") (class "Default")
      (node (ref "IC14") (pin "2") (pinfunction "CLK_2") (pintype "bidirectional"))
      (node (ref "IC6") (pin "1") (pinfunction "32KHZ_1") (pintype "bidirectional"))
      (node (ref "R29") (pin "2") (pinfunction "2_2") (pintype "passive"))
    )
    (net (code "6") (name "A") (class "Default")
      (node (ref "IC5") (pin "4") (pinfunction "A_4") (pintype "output"))
      (node (ref "IC7") (pin "1") (pinfunction "I0_1") (pintype "input"))
    )
    (net (code "7") (name "B") (class "Default")
      (node (ref "IC2") (pin "1") (pinfunction "I0_1") (pintype "input"))
      (node (ref "IC5") (pin "6") (pinfunction "B_6") (pintype "output"))
    )
    (net (code "8") (name "BUS_CONTROL") (class "Default")
      (node (ref "IC10") (pin "1") (pinfunction "OE_1") (pintype "input"))
      (node (ref "IC15") (pin "1") (pinfunction "OE_1") (pintype "input"))
      (node (ref "IC16") (pin "1") (pinfunction "OE_1") (pintype "input"))
      (node (ref "IC17") (pin "1") (pinfunction "OE_1") (pintype "input"))
      (node (ref "IC18") (pin "25") (pinfunction "RE0/AN5/*RD_25") (pintype "passive"))
    )
    (net (code "9") (name "C") (class "Default")
      (node (ref "IC5") (pin "7") (pinfunction "C_7") (pintype "output"))
      (node (ref "IC8") (pin "1") (pinfunction "I0_1") (pintype "input"))
    )
    (net (code "10") (name "CNTRL") (class "Default")
      (node (ref "IC18") (pin "21") (pinfunction "RA2/VREF-/AN2/C2INC_21") (pintype "passive"))
      (node (ref "IC5") (pin "11") (pinfunction "CNTL_11") (pintype "input"))
    )
    (net (code "11") (name "COUNT_CCW") (class "Default")
      (node (ref "IC18") (pin "24") (pinfunction "RA5/AN4//HLVDIN/T1CKI/*SS_24") (pintype "passive"))
      (node (ref "IC22") (pin "4") (pinfunction "O_4") (pintype "output"))
    )
    (net (code "12") (name "COUNT_CW") (class "Default")
      (node (ref "IC18") (pin "15") (pinfunction "RB5/TOCKI/T3CKI/CCP5/KBI1_15") (pintype "passive"))
      (node (ref "IC23") (pin "4") (pinfunction "O_4") (pintype "output"))
    )
    (net (code "13") (name "CW{slash}~{CCW}") (class "Default")
      (node (ref "IC16") (pin "4") (pinfunction "O_4") (pintype "tri_state"))
      (node (ref "IC17") (pin "4") (pinfunction "O_4") (pintype "output"))
      (node (ref "IC5") (pin "17") (pinfunction "CW/CCW_17") (pintype "input"))
    )
    (net (code "14") (name "D") (class "Default")
      (node (ref "IC5") (pin "9") (pinfunction "D_9") (pintype "output"))
      (node (ref "IC9") (pin "1") (pinfunction "I0_1") (pintype "input"))
    )
    (net (code "15") (name "D0") (class "Default")
      (node (ref "IC14") (pin "1") (pinfunction "D0_1") (pintype "bidirectional"))
      (node (ref "IC18") (pin "38") (pinfunction "RD0/C1INA/PSP0_38") (pintype "passive"))
    )
    (net (code "16") (name "D1") (class "Default")
      (node (ref "IC14") (pin "19") (pinfunction "D1_19") (pintype "bidirectional"))
      (node (ref "IC18") (pin "39") (pinfunction "RD1/C1INB/PSP1_39") (pintype "passive"))
    )
    (net (code "17") (name "D2") (class "Default")
      (node (ref "IC14") (pin "18") (pinfunction "D2_18") (pintype "bidirectional"))
      (node (ref "IC18") (pin "40") (pinfunction "RD2/C2INA/PSP2_40") (pintype "passive"))
    )
    (net (code "18") (name "D3") (class "Default")
      (node (ref "IC14") (pin "17") (pinfunction "D3_17") (pintype "bidirectional"))
      (node (ref "IC18") (pin "41") (pinfunction "RD3/C2INB/CTMUI/PSP3_41") (pintype "passive"))
    )
    (net (code "19") (name "D4") (class "Default")
      (node (ref "IC14") (pin "14") (pinfunction "D4_14") (pintype "bidirectional"))
      (node (ref "IC18") (pin "2") (pinfunction "RD4/ECCP1/P1A/PSP4_2") (pintype "passive"))
    )
    (net (code "20") (name "D5") (class "Default")
      (node (ref "IC14") (pin "13") (pinfunction "D5_13") (pintype "bidirectional"))
      (node (ref "IC18") (pin "3") (pinfunction "RD5/PSP5/P1B_3") (pintype "passive"))
    )
    (net (code "21") (name "D6") (class "Default")
      (node (ref "IC14") (pin "12") (pinfunction "D6_12") (pintype "bidirectional"))
      (node (ref "IC18") (pin "4") (pinfunction "RD6/TX2/CK2/P1C/PSP6_4") (pintype "passive"))
    )
    (net (code "22") (name "D7") (class "Default")
      (node (ref "IC14") (pin "11") (pinfunction "D7_11") (pintype "bidirectional"))
      (node (ref "IC18") (pin "5") (pinfunction "RD7/RX2/DT2/P1D/PSP7_5") (pintype "passive"))
    )
    (net (code "23") (name "DATA_SELECT") (class "Default")
      (node (ref "IC14") (pin "3") (pinfunction "SEL_3") (pintype "bidirectional"))
      (node (ref "IC18") (pin "37") (pinfunction "RC3/REFO/SCL/SCK_37") (pintype "passive"))
    )
    (net (code "24") (name "ENABLE_DRIVE") (class "Default")
      (node (ref "IC18") (pin "19") (pinfunction "RA0/CVREF/AN0/ULPWU_19") (pintype "passive"))
      (node (ref "IC19") (pin "1") (pinfunction "I0_1") (pintype "input"))
      (node (ref "IC19") (pin "2") (pinfunction "I1_2") (pintype "input"))
      (node (ref "IC5") (pin "10") (pinfunction "ENABLE_10") (pintype "input"))
    )
    (net (code "25") (name "EXT_DIRECTION") (class "Default")
      (node (ref "IC12") (pin "2") (pinfunction "I_2") (pintype "input"))
      (node (ref "IC16") (pin "2") (pinfunction "I_2") (pintype "input"))
      (node (ref "IC18") (pin "14") (pinfunction "RB4/AN9/CTPLS/KBIO_14") (pintype "passive"))
      (node (ref "IC23") (pin "1") (pinfunction "I0_1") (pintype "input"))
      (node (ref "R6") (pin "2") (pinfunction "2_2") (pintype "passive"))
    )
    (net (code "26") (name "EXT_TRIGGER") (class "Default")
      (node (ref "IC10") (pin "2") (pinfunction "I_2") (pintype "input"))
      (node (ref "IC18") (pin "11") (pinfunction "RB3/CANRX/CTED2/INT3_11") (pintype "passive"))
      (node (ref "IC25") (pin "1") (pinfunction "TRIG_1") (pintype "bidirectional"))
      (node (ref "R7") (pin "2") (pinfunction "2_2") (pintype "passive"))
    )
    (net (code "27") (name "GND") (class "Default")
      (node (ref "C1") (pin "2") (pinfunction "2_2") (pintype "passive"))
      (node (ref "C10") (pin "C") (pinfunction "-_C") (pintype "passive"))
      (node (ref "C11") (pin "C") (pinfunction "-_C") (pintype "passive"))
      (node (ref "C12") (pin "2") (pinfunction "2_2") (pintype "passive"))
      (node (ref "C13") (pin "2") (pinfunction "2_2") (pintype "passive"))
      (node (ref "C14") (pin "-") (pinfunction "-_-") (pintype "passive"))
      (node (ref "C15") (pin "1") (pinfunction "1_1") (pintype "passive"))
      (node (ref "C16") (pin "2") (pinfunction "2_2") (pintype "passive"))
      (node (ref "C17") (pin "2") (pinfunction "2_2") (pintype "passive"))
      (node (ref "C18") (pin "2") (pinfunction "2_2") (pintype "passive"))
      (node (ref "C19") (pin "2") (pinfunction "2_2") (pintype "passive"))
      (node (ref "C2") (pin "2") (pinfunction "2_2") (pintype "passive"))
      (node (ref "C20") (pin "2") (pinfunction "2_2") (pintype "passive"))
      (node (ref "C21") (pin "2") (pinfunction "2_2") (pintype "passive"))
      (node (ref "C22") (pin "1") (pinfunction "1_1") (pintype "passive"))
      (node (ref "C23") (pin "2") (pinfunction "2_2") (pintype "passive"))
      (node (ref "C24") (pin "C") (pinfunction "-_C") (pintype "passive"))
      (node (ref "C25") (pin "2") (pinfunction "2_2") (pintype "passive"))
      (node (ref "C26") (pin "2") (pinfunction "2_2") (pintype "passive"))
      (node (ref "C27") (pin "2") (pinfunction "2_2") (pintype "passive"))
      (node (ref "C28") (pin "2") (pinfunction "2_2") (pintype "passive"))
      (node (ref "C29") (pin "2") (pinfunction "2_2") (pintype "passive"))
      (node (ref "C3") (pin "2") (pinfunction "2_2") (pintype "passive"))
      (node (ref "C30") (pin "-") (pinfunction "-_-") (pintype "passive"))
      (node (ref "C31") (pin "2") (pinfunction "2_2") (pintype "passive"))
      (node (ref "C32") (pin "2") (pinfunction "2_2") (pintype "passive"))
      (node (ref "C33") (pin "2") (pinfunction "2_2") (pintype "passive"))
      (node (ref "C34") (pin "2") (pinfunction "2_2") (pintype "passive"))
      (node (ref "C35") (pin "2") (pinfunction "2_2") (pintype "passive"))
      (node (ref "C36") (pin "2") (pinfunction "2_2") (pintype "passive"))
      (node (ref "C37") (pin "2") (pinfunction "2_2") (pintype "passive"))
      (node (ref "C38") (pin "2") (pinfunction "2_2") (pintype "passive"))
      (node (ref "C4") (pin "-") (pinfunction "-_-") (pintype "passive"))
      (node (ref "C5") (pin "2") (pinfunction "2_2") (pintype "passive"))
      (node (ref "C6") (pin "2") (pinfunction "2_2") (pintype "passive"))
      (node (ref "C7") (pin "C") (pinfunction "-_C") (pintype "passive"))
      (node (ref "C8") (pin "2") (pinfunction "2_2") (pintype "passive"))
      (node (ref "C9") (pin "2") (pinfunction "2_2") (pintype "passive"))
      (node (ref "D10") (pin "A") (pinfunction "A_A") (pintype "passive"))
      (node (ref "D14") (pin "A") (pinfunction "A_A") (pintype "passive"))
      (node (ref "D17") (pin "A") (pinfunction "A_A") (pintype "passive"))
      (node (ref "D21") (pin "A") (pinfunction "A_A") (pintype "passive"))
      (node (ref "IC1") (pin "3") (pinfunction "GND_3") (pintype "passive"))
      (node (ref "IC10") (pin "3") (pinfunction "GND_3") (pintype "power_in"))
      (node (ref "IC11") (pin "3") (pinfunction "GND_3") (pintype "power_in"))
      (node (ref "IC12") (pin "3") (pinfunction "GND_3") (pintype "power_in"))
      (node (ref "IC13") (pin "3") (pinfunction "GND_3") (pintype "power_in"))
      (node (ref "IC14") (pin "10") (pinfunction "VSS_10") (pintype "bidirectional"))
      (node (ref "IC15") (pin "3") (pinfunction "GND_3") (pintype "power_in"))
      (node (ref "IC16") (pin "3") (pinfunction "GND_3") (pintype "power_in"))
      (node (ref "IC17") (pin "3") (pinfunction "GND_3") (pintype "power_in"))
      (node (ref "IC18") (pin "29") (pinfunction "VSS_29") (pintype "passive"))
      (node (ref "IC18") (pin "6") (pinfunction "VSS_2_6") (pintype "passive"))
      (node (ref "IC19") (pin "3") (pinfunction "GND_3") (pintype "power_in"))
      (node (ref "IC2") (pin "3") (pinfunction "GND_3") (pintype "power_in"))
      (node (ref "IC22") (pin "3") (pinfunction "GND_3") (pintype "power_in"))
      (node (ref "IC23") (pin "3") (pinfunction "GND_3") (pintype "power_in"))
      (node (ref "IC25") (pin "2") (pinfunction "GND_2") (pintype "bidirectional"))
      (node (ref "IC3") (pin "13") (pinfunction "GND_13") (pintype "power_in"))
      (node (ref "IC3") (pin "5") (pinfunction "GND_5") (pintype "power_in"))
      (node (ref "IC4") (pin "1") (pinfunction "A0_1") (pintype "input"))
      (node (ref "IC4") (pin "2") (pinfunction "A1_2") (pintype "input"))
      (node (ref "IC4") (pin "4") (pinfunction "GND_4") (pintype "power_in"))
      (node (ref "IC4") (pin "7") (pinfunction "WP_7") (pintype "input"))
      (node (ref "IC5") (pin "2") (pinfunction "GND_2") (pintype "power_in"))
      (node (ref "IC6") (pin "5") (pinfunction "GND_5") (pintype "bidirectional"))
      (node (ref "IC7") (pin "3") (pinfunction "GND_3") (pintype "power_in"))
      (node (ref "IC8") (pin "3") (pinfunction "GND_3") (pintype "power_in"))
      (node (ref "IC9") (pin "3") (pinfunction "GND_3") (pintype "power_in"))
      (node (ref "LED2") (pin "C") (pinfunction "C_C") (pintype "passive"))
      (node (ref "LED3") (pin "C") (pinfunction "C_C") (pintype "passive"))
      (node (ref "LED4") (pin "C") (pinfunction "C_C") (pintype "passive"))
      (node (ref "LED5") (pin "C") (pinfunction "C_C") (pintype "passive"))
      (node (ref "LED6") (pin "C") (pinfunction "C_C") (pintype "passive"))
      (node (ref "LED8") (pin "C") (pinfunction "C_C") (pintype "passive"))
      (node (ref "R11") (pin "1") (pinfunction "1_1") (pintype "passive"))
      (node (ref "R13") (pin "1") (pinfunction "1_1") (pintype "passive"))
      (node (ref "R15") (pin "1") (pinfunction "1_1") (pintype "passive"))
      (node (ref "R19") (pin "1") (pinfunction "1_1") (pintype "passive"))
      (node (ref "R22") (pin "1") (pinfunction "1_1") (pintype "passive"))
      (node (ref "R24") (pin "1") (pinfunction "1_1") (pintype "passive"))
      (node (ref "R32") (pin "1") (pinfunction "1_1") (pintype "passive"))
      (node (ref "R38") (pin "1") (pinfunction "1_1") (pintype "passive"))
      (node (ref "R4") (pin "1") (pinfunction "1_1") (pintype "passive"))
      (node (ref "R44") (pin "1") (pinfunction "1_1") (pintype "passive"))
      (node (ref "R5") (pin "1") (pinfunction "1_1") (pintype "passive"))
      (node (ref "TP2") (pin "P$1") (pinfunction "P$1_P$1") (pintype "bidirectional"))
      (node (ref "X1") (pin "4") (pinfunction "S_4") (pintype "passive"))
      (node (ref "X10") (pin "3") (pinfunction "S_3") (pintype "passive"))
      (node (ref "X12") (pin "2") (pinfunction "S_2") (pintype "passive"))
      (node (ref "X3") (pin "2") (pinfunction "2_2") (pintype "passive"))
      (node (ref "X4") (pin "2") (pinfunction "2_2") (pintype "passive"))
      (node (ref "X5") (pin "3") (pinfunction "S_3") (pintype "passive"))
      (node (ref "X6") (pin "2") (pinfunction "S_2") (pintype "passive"))
      (node (ref "X7") (pin "5") (pinfunction "S_5") (pintype "passive"))
      (node (ref "X8") (pin "3") (pinfunction "S_3") (pintype "passive"))
    )
    (net (code "28") (name "HALF{slash}~{FULL}") (class "Default")
      (node (ref "IC18") (pin "22") (pinfunction "RA3/AN3/VREF+_22") (pintype "passive"))
      (node (ref "IC5") (pin "19") (pinfunction "H/F_19") (pintype "input"))
    )
    (net (code "29") (name "I2C_CLK") (class "Default")
      (node (ref "IC4") (pin "6") (pinfunction "SCL_6") (pintype "input"))
      (node (ref "IC6") (pin "8") (pinfunction "SCL_8") (pintype "bidirectional"))
      (node (ref "R27") (pin "1") (pinfunction "1_1") (pintype "passive"))
      (node (ref "R40") (pin "2") (pinfunction "2_2") (pintype "passive"))
      (node (ref "X12") (pin "4") (pinfunction "S_4") (pintype "passive"))
    )
    (net (code "30") (name "I2C_DATA") (class "Default")
      (node (ref "IC4") (pin "5") (pinfunction "SDA_5") (pintype "bidirectional"))
      (node (ref "IC6") (pin "7") (pinfunction "SDA_7") (pintype "bidirectional"))
      (node (ref "R31") (pin "1") (pinfunction "1_1") (pintype "passive"))
      (node (ref "R33") (pin "1") (pinfunction "1_1") (pintype "passive"))
      (node (ref "X12") (pin "3") (pinfunction "S_3") (pintype "passive"))
    )
    (net (code "31") (name "ILLUMINATE") (class "Default")
      (node (ref "IC11") (pin "1") (pinfunction "I0_1") (pintype "input"))
      (node (ref "IC11") (pin "2") (pinfunction "I1_2") (pintype "input"))
      (node (ref "IC13") (pin "1") (pinfunction "I0_1") (pintype "input"))
      (node (ref "IC13") (pin "2") (pinfunction "I1_2") (pintype "input"))
      (node (ref "IC18") (pin "10") (pinfunction "RB2/CANTX/CTED1/INT2_10") (pintype "passive"))
    )
    (net (code "32") (name "INDEX") (class "Default")
      (node (ref "X7") (pin "4") (pinfunction "S_4") (pintype "passive"))
    )
    (net (code "33") (name "LEFT") (class "Default")
      (node (ref "IC18") (pin "9") (pinfunction "RB1/AN8/CTDIN/INT1_9") (pintype "passive"))
      (node (ref "R41") (pin "2") (pinfunction "2_2") (pintype "passive"))
    )
    (net (code "34") (name "Net-(C24-+)") (class "Default")
      (node (ref "C24") (pin "A") (pinfunction "+_A") (pintype "passive"))
      (node (ref "IC18") (pin "23") (pinfunction "VDDCORE/VCAP_23") (pintype "passive"))
    )
    (net (code "35") (name "Net-(D1-C)") (class "Default")
      (node (ref "D1") (pin "3") (pinfunction "C_3") (pintype "passive"))
      (node (ref "R39") (pin "1") (pinfunction "1_1") (pintype "passive"))
    )
    (net (code "36") (name "Net-(D12-C)") (class "Default")
      (node (ref "D12") (pin "3") (pinfunction "C_3") (pintype "passive"))
      (node (ref "R2") (pin "2") (pinfunction "2_2") (pintype "passive"))
      (node (ref "R3") (pin "2") (pinfunction "2_2") (pintype "passive"))
      (node (ref "T2") (pin "1") (pinfunction "G_1") (pintype "passive"))
    )
    (net (code "37") (name "Net-(D16-C)") (class "Default")
      (node (ref "D16") (pin "3") (pinfunction "C_3") (pintype "passive"))
      (node (ref "R17") (pin "2") (pinfunction "2_2") (pintype "passive"))
      (node (ref "R20") (pin "2") (pinfunction "2_2") (pintype "passive"))
      (node (ref "T3") (pin "1") (pinfunction "G_1") (pintype "passive"))
    )
    (net (code "38") (name "Net-(D18-C)") (class "Default")
      (node (ref "D18") (pin "3") (pinfunction "C_3") (pintype "passive"))
      (node (ref "R1") (pin "2") (pinfunction "2_2") (pintype "passive"))
      (node (ref "R16") (pin "2") (pinfunction "2_2") (pintype "passive"))
      (node (ref "T1") (pin "1") (pinfunction "G_1") (pintype "passive"))
    )
    (net (code "39") (name "Net-(D20-C)") (class "Default")
      (node (ref "D20") (pin "3") (pinfunction "C_3") (pintype "passive"))
      (node (ref "R21") (pin "2") (pinfunction "2_2") (pintype "passive"))
      (node (ref "R23") (pin "2") (pinfunction "2_2") (pintype "passive"))
      (node (ref "T4") (pin "1") (pinfunction "G_1") (pintype "passive"))
    )
    (net (code "40") (name "Net-(IC2A-O)") (class "Default")
      (node (ref "IC2") (pin "4") (pinfunction "O_4") (pintype "output"))
      (node (ref "R3") (pin "1") (pinfunction "1_1") (pintype "passive"))
    )
    (net (code "41") (name "Net-(IC3-CBUS0)") (class "Default")
      (node (ref "IC3") (pin "15") (pinfunction "CBUS0_15") (pintype "bidirectional"))
      (node (ref "R10") (pin "1") (pinfunction "1_1") (pintype "passive"))
      (node (ref "R13") (pin "2") (pinfunction "2_2") (pintype "passive"))
    )
    (net (code "42") (name "Net-(IC3-USBDM)") (class "Default")
      (node (ref "IC3") (pin "9") (pinfunction "USBDM_9") (pintype "input"))
      (node (ref "R9") (pin "1") (pinfunction "1_1") (pintype "passive"))
    )
    (net (code "43") (name "Net-(IC3-USBDP)") (class "Default")
      (node (ref "IC3") (pin "8") (pinfunction "USBDP_8") (pintype "input"))
      (node (ref "R8") (pin "1") (pinfunction "1_1") (pintype "passive"))
    )
    (net (code "44") (name "Net-(IC5-HOME)") (class "Default")
      (node (ref "IC5") (pin "3") (pinfunction "HOME_3") (pintype "output"))
      (node (ref "LED6") (pin "A") (pinfunction "A_A") (pintype "passive"))
      (node (ref "R28") (pin "1") (pinfunction "1_1") (pintype "passive"))
    )
    (net (code "45") (name "Net-(IC5-SENS1)") (class "Default")
      (node (ref "C3") (pin "1") (pinfunction "1_1") (pintype "passive"))
      (node (ref "IC5") (pin "14") (pinfunction "SENS1_14") (pintype "output"))
      (node (ref "R25") (pin "2") (pinfunction "2_2") (pintype "passive"))
    )
    (net (code "46") (name "Net-(IC5-SENS2)") (class "Default")
      (node (ref "C12") (pin "1") (pinfunction "1_1") (pintype "passive"))
      (node (ref "IC5") (pin "13") (pinfunction "SENS2_13") (pintype "output"))
      (node (ref "R26") (pin "2") (pinfunction "2_2") (pintype "passive"))
    )
    (net (code "47") (name "Net-(IC6-VBAT)") (class "Default")
      (node (ref "C30") (pin "+") (pinfunction "+_+") (pintype "passive"))
      (node (ref "IC6") (pin "6") (pinfunction "VBAT_6") (pintype "bidirectional"))
      (node (ref "R39") (pin "2") (pinfunction "2_2") (pintype "passive"))
    )
    (net (code "48") (name "Net-(IC7A-O)") (class "Default")
      (node (ref "IC7") (pin "4") (pinfunction "O_4") (pintype "output"))
      (node (ref "R16") (pin "1") (pinfunction "1_1") (pintype "passive"))
    )
    (net (code "49") (name "Net-(IC8A-O)") (class "Default")
      (node (ref "IC8") (pin "4") (pinfunction "O_4") (pintype "output"))
      (node (ref "R20") (pin "1") (pinfunction "1_1") (pintype "passive"))
    )
    (net (code "50") (name "Net-(IC9A-O)") (class "Default")
      (node (ref "IC9") (pin "4") (pinfunction "O_4") (pintype "output"))
      (node (ref "R23") (pin "1") (pinfunction "1_1") (pintype "passive"))
    )
    (net (code "51") (name "Net-(IC11A-O)") (class "Default")
      (node (ref "IC11") (pin "4") (pinfunction "O_4") (pintype "output"))
      (node (ref "R34") (pin "2") (pinfunction "2_2") (pintype "passive"))
    )
    (net (code "52") (name "Net-(IC12A-O)") (class "Default")
      (node (ref "IC12") (pin "4") (pinfunction "O_4") (pintype "output"))
      (node (ref "IC22") (pin "1") (pinfunction "I0_1") (pintype "input"))
    )
    (net (code "53") (name "Net-(IC13A-O)") (class "Default")
      (node (ref "IC13") (pin "4") (pinfunction "O_4") (pintype "output"))
      (node (ref "R36") (pin "2") (pinfunction "2_2") (pintype "passive"))
    )
    (net (code "54") (name "Net-(IC14-U{slash}~{D})") (class "Default")
      (node (ref "IC14") (pin "5") (pinfunction "U/~{D}_5") (pintype "bidirectional"))
      (node (ref "R45") (pin "2") (pinfunction "2_2") (pintype "passive"))
    )
    (net (code "55") (name "Net-(IC18-OSC1{slash}CLKI{slash}RA7)") (class "Default")
      (node (ref "C15") (pin "2") (pinfunction "2_2") (pintype "passive"))
      (node (ref "IC18") (pin "30") (pinfunction "OSC1/CLKI/RA7_30") (pintype "passive"))
      (node (ref "Q1") (pin "1") (pinfunction "1_1") (pintype "passive"))
    )
    (net (code "56") (name "Net-(IC18-OSC2{slash}CLKO{slash}RA6)") (class "Default")
      (node (ref "C22") (pin "2") (pinfunction "2_2") (pintype "passive"))
      (node (ref "IC18") (pin "31") (pinfunction "OSC2/CLKO/RA6_31") (pintype "passive"))
      (node (ref "Q1") (pin "2") (pinfunction "2_2") (pintype "passive"))
    )
    (net (code "57") (name "Net-(IC18-RC0{slash}SOSCO{slash}SLCKI)") (class "Default")
      (node (ref "IC18") (pin "32") (pinfunction "RC0/SOSCO/SLCKI_32") (pintype "passive"))
      (node (ref "R40") (pin "1") (pinfunction "1_1") (pintype "passive"))
    )
    (net (code "58") (name "Net-(IC18-RC1{slash}SOSCI)") (class "Default")
      (node (ref "IC18") (pin "35") (pinfunction "RC1/SOSCI_35") (pintype "passive"))
      (node (ref "R33") (pin "2") (pinfunction "2_2") (pintype "passive"))
    )
    (net (code "59") (name "Net-(IC19A-O)") (class "Default")
      (node (ref "IC19") (pin "4") (pinfunction "O_4") (pintype "output"))
      (node (ref "LED7") (pin "2") (pinfunction "CR(2)_2") (pintype "passive"))
    )
    (net (code "60") (name "Net-(IC22A-I1)") (class "Default")
      (node (ref "IC22") (pin "2") (pinfunction "I1_2") (pintype "input"))
      (node (ref "IC23") (pin "2") (pinfunction "I1_2") (pintype "input"))
      (node (ref "IC25") (pin "6") (pinfunction "OUT_6") (pintype "bidirectional"))
    )
    (net (code "61") (name "Net-(IC25-DIV)") (class "Default")
      (node (ref "IC25") (pin "4") (pinfunction "DIV_4") (pintype "bidirectional"))
      (node (ref "R37") (pin "1") (pinfunction "1_1") (pintype "passive"))
      (node (ref "R38") (pin "2") (pinfunction "2_2") (pintype "passive"))
    )
    (net (code "62") (name "Net-(IC25-SET)") (class "Default")
      (node (ref "IC25") (pin "3") (pinfunction "SET_3") (pintype "bidirectional"))
      (node (ref "R44") (pin "2") (pinfunction "2_2") (pintype "passive"))
    )
    (net (code "63") (name "Net-(LED1-PadC)") (class "Default")
      (node (ref "LED1") (pin "C") (pinfunction "C_C") (pintype "passive"))
      (node (ref "R22") (pin "2") (pinfunction "2_2") (pintype "passive"))
    )
    (net (code "64") (name "Net-(LED2-PadA)") (class "Default")
      (node (ref "LED2") (pin "A") (pinfunction "A_A") (pintype "passive"))
      (node (ref "R2") (pin "1") (pinfunction "1_1") (pintype "passive"))
    )
    (net (code "65") (name "Net-(LED3-PadA)") (class "Default")
      (node (ref "LED3") (pin "A") (pinfunction "A_A") (pintype "passive"))
      (node (ref "R1") (pin "1") (pinfunction "1_1") (pintype "passive"))
    )
    (net (code "66") (name "Net-(LED4-PadA)") (class "Default")
      (node (ref "LED4") (pin "A") (pinfunction "A_A") (pintype "passive"))
      (node (ref "R17") (pin "1") (pinfunction "1_1") (pintype "passive"))
    )
    (net (code "67") (name "Net-(LED5-PadA)") (class "Default")
      (node (ref "LED5") (pin "A") (pinfunction "A_A") (pintype "passive"))
      (node (ref "R21") (pin "1") (pinfunction "1_1") (pintype "passive"))
    )
    (net (code "68") (name "Net-(LED7-CG(1))") (class "Default")
      (node (ref "LED7") (pin "1") (pinfunction "CG(1)_1") (pintype "passive"))
      (node (ref "R14") (pin "1") (pinfunction "1_1") (pintype "passive"))
      (node (ref "R15") (pin "2") (pinfunction "2_2") (pintype "passive"))
    )
    (net (code "69") (name "Net-(LED8-PadA)") (class "Default")
      (node (ref "LED8") (pin "A") (pinfunction "A_A") (pintype "passive"))
      (node (ref "R45") (pin "1") (pinfunction "1_1") (pintype "passive"))
    )
    (net (code "70") (name "Net-(LED10-PadC)") (class "Default")
      (node (ref "LED10") (pin "C") (pinfunction "C_C") (pintype "passive"))
      (node (ref "R32") (pin "2") (pinfunction "2_2") (pintype "passive"))
    )
    (net (code "71") (name "Net-(R4-Pad2)") (class "Default")
      (node (ref "R4") (pin "2") (pinfunction "2_2") (pintype "passive"))
      (node (ref "R6") (pin "1") (pinfunction "1_1") (pintype "passive"))
      (node (ref "X3") (pin "1") (pinfunction "1_1") (pintype "passive"))
    )
    (net (code "72") (name "Net-(R5-Pad2)") (class "Default")
      (node (ref "R5") (pin "2") (pinfunction "2_2") (pintype "passive"))
      (node (ref "R7") (pin "1") (pinfunction "1_1") (pintype "passive"))
      (node (ref "X4") (pin "1") (pinfunction "1_1") (pintype "passive"))
    )
    (net (code "73") (name "Net-(X1A-S)") (class "Default")
      (node (ref "R10") (pin "2") (pinfunction "2_2") (pintype "passive"))
      (node (ref "X1") (pin "1") (pinfunction "S_1") (pintype "passive"))
    )
    (net (code "74") (name "Net-(X1B-S)") (class "Default")
      (node (ref "C5") (pin "1") (pinfunction "1_1") (pintype "passive"))
      (node (ref "R9") (pin "2") (pinfunction "2_2") (pintype "passive"))
      (node (ref "X1") (pin "2") (pinfunction "S_2") (pintype "passive"))
    )
    (net (code "75") (name "Net-(X1C-S)") (class "Default")
      (node (ref "C6") (pin "1") (pinfunction "1_1") (pintype "passive"))
      (node (ref "R8") (pin "2") (pinfunction "2_2") (pintype "passive"))
      (node (ref "X1") (pin "3") (pinfunction "S_3") (pintype "passive"))
    )
    (net (code "76") (name "Net-(X8A-S)") (class "Default")
      (node (ref "R34") (pin "1") (pinfunction "1_1") (pintype "passive"))
      (node (ref "X8") (pin "1") (pinfunction "S_1") (pintype "passive"))
    )
    (net (code "77") (name "Net-(X8B-S)") (class "Default")
      (node (ref "R35") (pin "1") (pinfunction "1_1") (pintype "passive"))
      (node (ref "X8") (pin "2") (pinfunction "S_2") (pintype "passive"))
    )
    (net (code "78") (name "Net-(X10A-S)") (class "Default")
      (node (ref "R36") (pin "1") (pinfunction "1_1") (pintype "passive"))
      (node (ref "X10") (pin "1") (pinfunction "S_1") (pintype "passive"))
    )
    (net (code "79") (name "Net-(X10B-S)") (class "Default")
      (node (ref "R41") (pin "1") (pinfunction "1_1") (pintype "passive"))
      (node (ref "X10") (pin "2") (pinfunction "S_2") (pintype "passive"))
    )
    (net (code "80") (name "OSC") (class "Default")
      (node (ref "C1") (pin "1") (pinfunction "1_1") (pintype "passive"))
      (node (ref "IC5") (pin "16") (pinfunction "OSC_16") (pintype "bidirectional"))
      (node (ref "R12") (pin "1") (pinfunction "1_1") (pintype "passive"))
    )
    (net (code "81") (name "OUTA") (class "Default")
      (node (ref "D10") (pin "C") (pinfunction "C_C") (pintype "passive"))
      (node (ref "D13") (pin "A") (pinfunction "A_A") (pintype "passive"))
      (node (ref "T1") (pin "2") (pinfunction "D_2") (pintype "passive"))
      (node (ref "T1") (pin "4") (pinfunction "D_4") (pintype "passive"))
      (node (ref "X2") (pin "3") (pinfunction "S_3") (pintype "passive"))
    )
    (net (code "82") (name "OUTB") (class "Default")
      (node (ref "D11") (pin "A") (pinfunction "A_A") (pintype "passive"))
      (node (ref "D14") (pin "C") (pinfunction "C_C") (pintype "passive"))
      (node (ref "T2") (pin "2") (pinfunction "D_2") (pintype "passive"))
      (node (ref "T2") (pin "4") (pinfunction "D_4") (pintype "passive"))
      (node (ref "X2") (pin "4") (pinfunction "S_4") (pintype "passive"))
    )
    (net (code "83") (name "OUTC") (class "Default")
      (node (ref "D15") (pin "A") (pinfunction "A_A") (pintype "passive"))
      (node (ref "D17") (pin "C") (pinfunction "C_C") (pintype "passive"))
      (node (ref "T3") (pin "2") (pinfunction "D_2") (pintype "passive"))
      (node (ref "T3") (pin "4") (pinfunction "D_4") (pintype "passive"))
      (node (ref "X2") (pin "5") (pinfunction "S_5") (pintype "passive"))
    )
    (net (code "84") (name "OUTD") (class "Default")
      (node (ref "D19") (pin "A") (pinfunction "A_A") (pintype "passive"))
      (node (ref "D21") (pin "C") (pinfunction "C_C") (pintype "passive"))
      (node (ref "T4") (pin "2") (pinfunction "D_2") (pintype "passive"))
      (node (ref "T4") (pin "4") (pinfunction "D_4") (pintype "passive"))
      (node (ref "X2") (pin "6") (pinfunction "S_6") (pintype "passive"))
    )
    (net (code "85") (name "PGC(ICSPCLK)") (class "Default")
      (node (ref "IC18") (pin "16") (pinfunction "RB6/PGC/KBI2_16") (pintype "passive"))
      (node (ref "X5") (pin "5") (pinfunction "S_5") (pintype "passive"))
    )
    (net (code "86") (name "PGD(ICSPDAT)") (class "Default")
      (node (ref "IC18") (pin "17") (pinfunction "RB7/PGD/T3G/KBI3_17") (pintype "passive"))
      (node (ref "X5") (pin "4") (pinfunction "S_4") (pintype "passive"))
    )
    (net (code "87") (name "PGM(LVP)") (class "Default")
      (node (ref "X5") (pin "6") (pinfunction "S_6") (pintype "passive"))
    )
    (net (code "88") (name "PIC_DIRECTION") (class "Default")
      (node (ref "IC17") (pin "2") (pinfunction "I_2") (pintype "input"))
      (node (ref "IC18") (pin "27") (pinfunction "RE2/AN7/C2OUT/*CS_27") (pintype "passive"))
    )
    (net (code "89") (name "PIC_STEP") (class "Default")
      (node (ref "IC15") (pin "2") (pinfunction "I_2") (pintype "input"))
      (node (ref "IC18") (pin "26") (pinfunction "RE1/AN6/C1OUT/*WR_26") (pintype "passive"))
    )
    (net (code "90") (name "QA") (class "Default")
      (node (ref "IC14") (pin "9") (pinfunction "CHA_9") (pintype "bidirectional"))
      (node (ref "X7") (pin "3") (pinfunction "S_3") (pintype "passive"))
    )
    (net (code "91") (name "QB") (class "Default")
      (node (ref "IC14") (pin "8") (pinfunction "CHB_8") (pintype "bidirectional"))
      (node (ref "X7") (pin "1") (pinfunction "S_1") (pintype "passive"))
    )
    (net (code "92") (name "RIGHT") (class "Default")
      (node (ref "IC18") (pin "8") (pinfunction "RB0/AN10/FLT0/INT0_8") (pintype "passive"))
      (node (ref "R35") (pin "2") (pinfunction "2_2") (pintype "passive"))
    )
    (net (code "93") (name "RX") (class "Default")
      (node (ref "IC18") (pin "1") (pinfunction "RC7/CANRX/RX1/DT1/CCP4_1") (pintype "passive"))
      (node (ref "IC3") (pin "1") (pinfunction "TXD_1") (pintype "output"))
    )
    (net (code "94") (name "SEN_1") (class "Default")
      (node (ref "D12") (pin "1") (pinfunction "A_1") (pintype "passive"))
      (node (ref "D18") (pin "1") (pinfunction "A_1") (pintype "passive"))
      (node (ref "R11") (pin "2") (pinfunction "2_2") (pintype "passive"))
      (node (ref "R25") (pin "1") (pinfunction "1_1") (pintype "passive"))
      (node (ref "T1") (pin "3") (pinfunction "S_3") (pintype "passive"))
      (node (ref "T2") (pin "3") (pinfunction "S_3") (pintype "passive"))
    )
    (net (code "95") (name "SEN_2") (class "Default")
      (node (ref "D16") (pin "1") (pinfunction "A_1") (pintype "passive"))
      (node (ref "D20") (pin "1") (pinfunction "A_1") (pintype "passive"))
      (node (ref "R24") (pin "2") (pinfunction "2_2") (pintype "passive"))
      (node (ref "R26") (pin "1") (pinfunction "1_1") (pintype "passive"))
      (node (ref "T3") (pin "3") (pinfunction "S_3") (pintype "passive"))
      (node (ref "T4") (pin "3") (pinfunction "S_3") (pintype "passive"))
    )
    (net (code "96") (name "STEP") (class "Default")
      (node (ref "IC10") (pin "4") (pinfunction "O_4") (pintype "tri_state"))
      (node (ref "IC15") (pin "4") (pinfunction "O_4") (pintype "output"))
      (node (ref "IC5") (pin "18") (pinfunction "CLOCK_18") (pintype "input"))
    )
    (net (code "97") (name "TX") (class "Default")
      (node (ref "IC18") (pin "44") (pinfunction "RC6/CANTX/TX1/CK1/CCP3_44") (pintype "passive"))
      (node (ref "IC3") (pin "4") (pinfunction "RXD_4") (pintype "input"))
    )
    (net (code "98") (name "VPP{slash}~{MCLR}") (class "Default")
      (node (ref "IC18") (pin "18") (pinfunction "*MCLR/RE3_18") (pintype "passive"))
      (node (ref "X5") (pin "1") (pinfunction "S_1") (pintype "passive"))
    )
    (net (code "99") (name "VREF") (class "Default")
      (node (ref "C8") (pin "1") (pinfunction "1_1") (pintype "passive"))
      (node (ref "IC5") (pin "15") (pinfunction "VREF_15") (pintype "input"))
      (node (ref "R18") (pin "1") (pinfunction "1_1") (pintype "passive"))
      (node (ref "R19") (pin "2") (pinfunction "2_2") (pintype "passive"))
    )
    (net (code "100") (name "unconnected-(IC3-CBUS1-Pad14)") (class "Default")
      (node (ref "IC3") (pin "14") (pinfunction "CBUS1_14") (pintype "bidirectional"))
    )
    (net (code "101") (name "unconnected-(IC3-CBUS2-Pad7)") (class "Default")
      (node (ref "IC3") (pin "7") (pinfunction "CBUS2_7") (pintype "bidirectional"))
    )
    (net (code "102") (name "unconnected-(IC3-CBUS3-Pad16)") (class "Default")
      (node (ref "IC3") (pin "16") (pinfunction "CBUS3_16") (pintype "bidirectional"))
    )
    (net (code "103") (name "unconnected-(IC3-~{CTS}-Pad6)") (class "Default")
      (node (ref "IC3") (pin "6") (pinfunction "~{CTS}_6") (pintype "input"))
    )
    (net (code "104") (name "unconnected-(IC3-~{RTS}-Pad2)") (class "Default")
      (node (ref "IC3") (pin "2") (pinfunction "~{RTS}_2") (pintype "output"))
    )
    (net (code "105") (name "unconnected-(IC5-SYNC-Pad1)") (class "Default")
      (node (ref "IC5") (pin "1") (pinfunction "SYNC_1") (pintype "output"))
    )
    (net (code "106") (name "unconnected-(IC6-~{RST}-Pad4)") (class "Default")
      (node (ref "IC6") (pin "4") (pinfunction "~{RST}_4") (pintype "bidirectional"))
    )
    (net (code "107") (name "unconnected-(IC14-CNTCAS-Pad15)") (class "Default")
      (node (ref "IC14") (pin "15") (pinfunction "CNTCAS_15") (pintype "bidirectional"))
    )
    (net (code "108") (name "unconnected-(IC14-CNTDCDR-Pad16)") (class "Default")
      (node (ref "IC14") (pin "16") (pinfunction "CNTDCDR_16") (pintype "bidirectional"))
    )
    (net (code "109") (name "unconnected-(IC18-NC-Pad34)") (class "Default")
      (node (ref "IC18") (pin "34") (pinfunction "NC_34") (pintype "passive"))
    )
    (net (code "110") (name "unconnected-(IC18-NC_2-Pad12)") (class "Default")
      (node (ref "IC18") (pin "12") (pinfunction "NC_2_12") (pintype "passive"))
    )
    (net (code "111") (name "unconnected-(IC18-NC_3-Pad13)") (class "Default")
      (node (ref "IC18") (pin "13") (pinfunction "NC_3_13") (pintype "passive"))
    )
    (net (code "112") (name "unconnected-(IC18-NC_4-Pad33)") (class "Default")
      (node (ref "IC18") (pin "33") (pinfunction "NC_4_33") (pintype "passive"))
    )
    (net (code "113") (name "unconnected-(X1E-S-Pad5)") (class "Default")
      (node (ref "X1") (pin "5") (pinfunction "S_5") (pintype "passive"))
    )
    (net (code "114") (name "~{INH1}") (class "Default")
      (node (ref "IC2") (pin "2") (pinfunction "I1_2") (pintype "input"))
      (node (ref "IC5") (pin "5") (pinfunction "INH1_5") (pintype "output"))
      (node (ref "IC7") (pin "2") (pinfunction "I1_2") (pintype "input"))
    )
    (net (code "115") (name "~{INH2}") (class "Default")
      (node (ref "IC5") (pin "8") (pinfunction "INH2_8") (pintype "output"))
      (node (ref "IC8") (pin "2") (pinfunction "I1_2") (pintype "input"))
      (node (ref "IC9") (pin "2") (pinfunction "I1_2") (pintype "input"))
    )
    (net (code "116") (name "~{READ_COUNTER}") (class "Default")
      (node (ref "IC14") (pin "4") (pinfunction "~{OE}_4") (pintype "bidirectional"))
      (node (ref "IC18") (pin "42") (pinfunction "RC4/SDI/SDA_42") (pintype "passive"))
    )
    (net (code "117") (name "~{RESET_COUNTER}") (class "Default")
      (node (ref "IC14") (pin "7") (pinfunction "~{RST}_7") (pintype "bidirectional"))
      (node (ref "IC18") (pin "43") (pinfunction "RC5/SDO_43") (pintype "passive"))
    )
    (net (code "118") (name "~{RESET_DRIVE}") (class "Default")
      (node (ref "IC18") (pin "20") (pinfunction "RA1/AN1/C1INC_20") (pintype "passive"))
      (node (ref "IC5") (pin "20") (pinfunction "RESET_20") (pintype "input"))
    )
  )
)
